# IceLogicBus.net
KiCad netlist of a schematic drawn in EAGLE
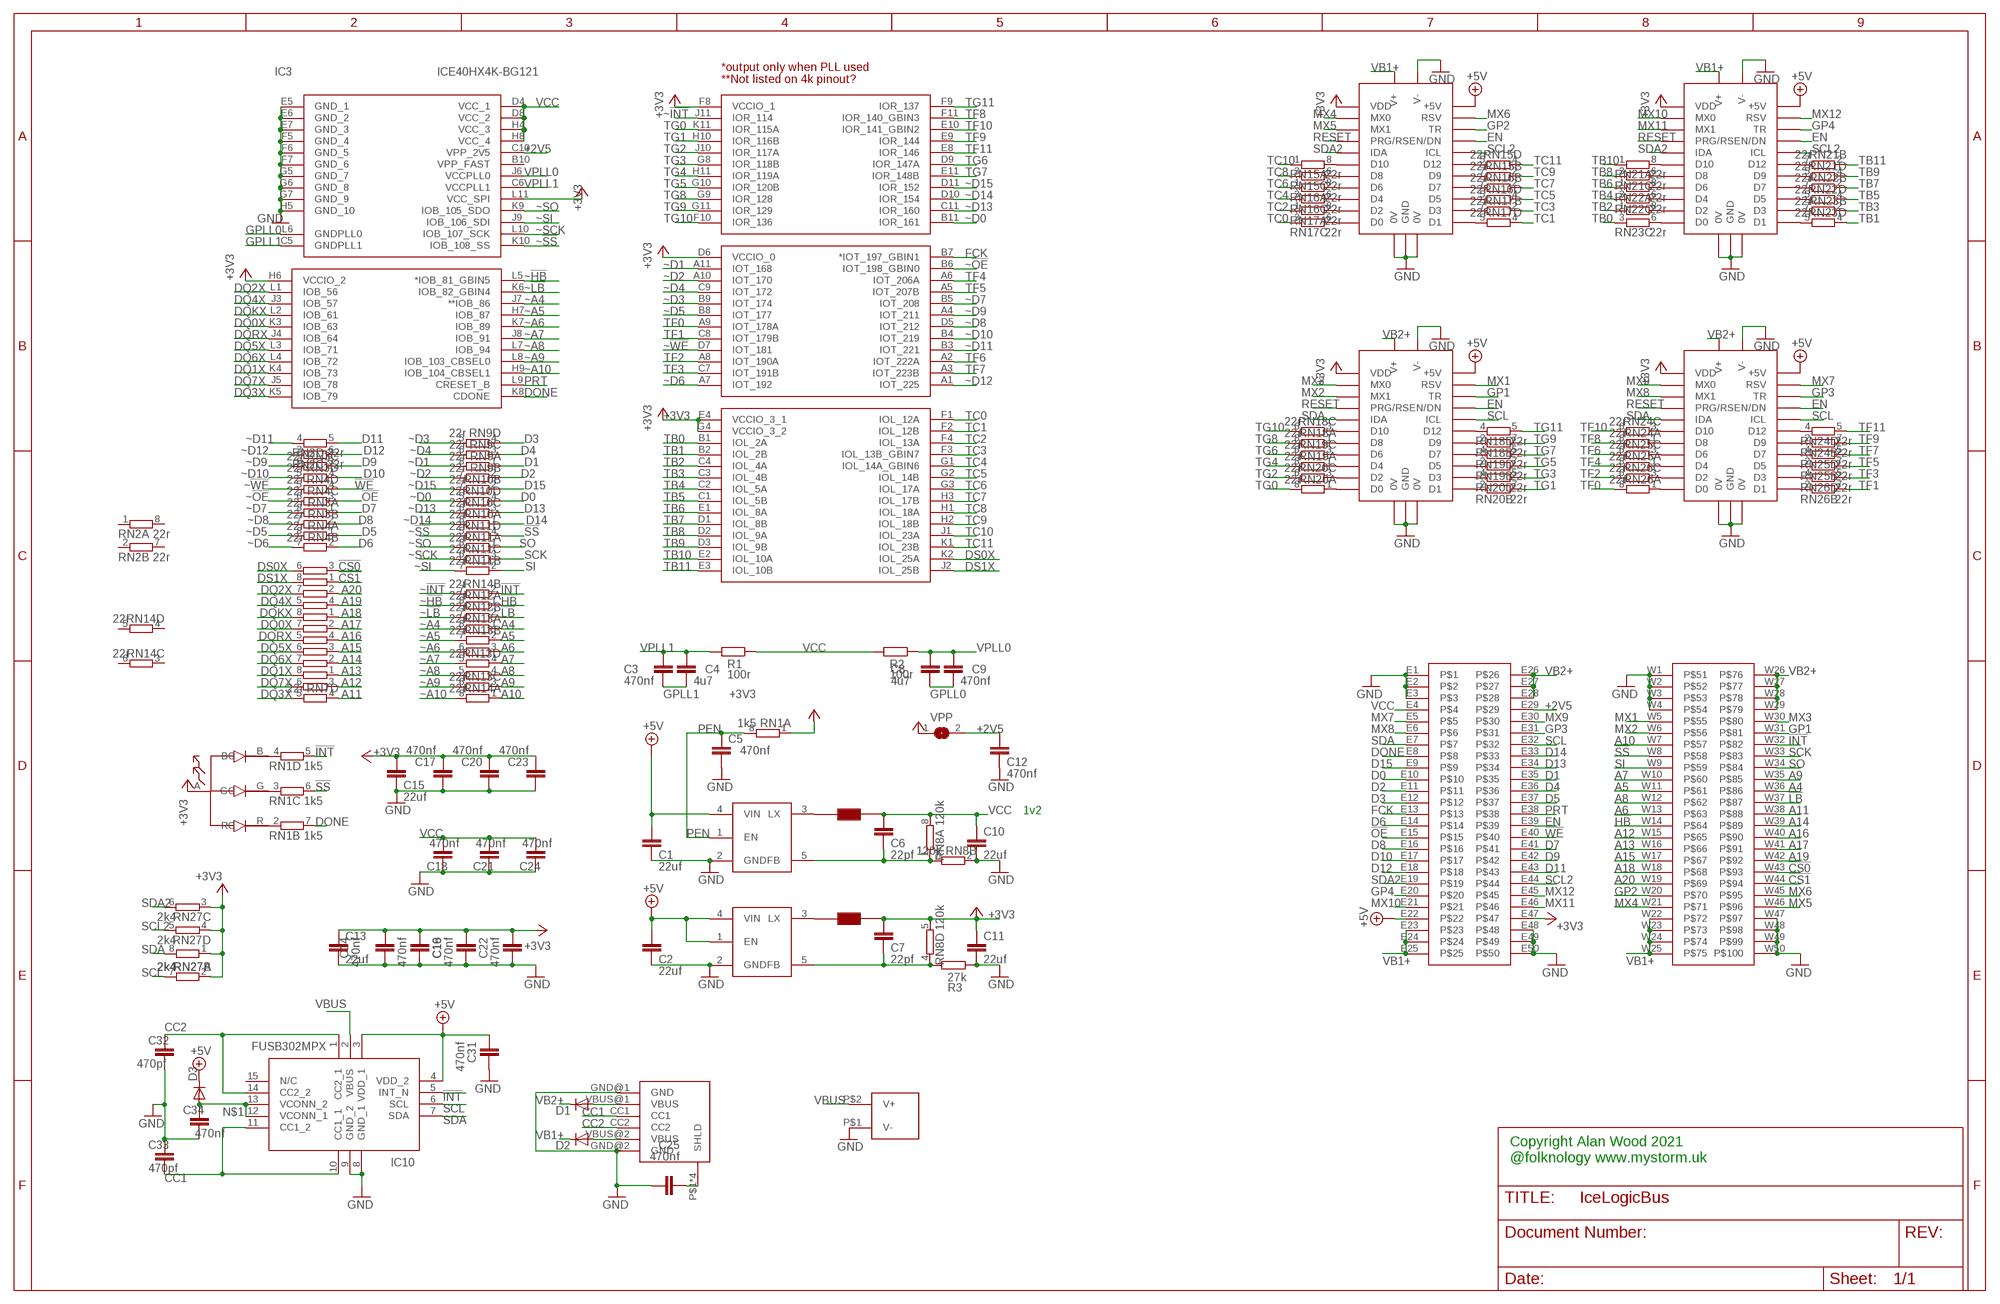
[diagram p0: schematic, sheet 1]

(export (version "E")
  (design (tool "Eeschema 10.0.6"))
  (components
    (comp (ref "C1")
      (value "22uf")
      (footprint "eagle-import:C0603")
      (libsource (lib "eagle-import") (part "C-EUC0603"))
    )
    (comp (ref "C2")
      (value "22uf")
      (footprint "eagle-import:C0603")
      (libsource (lib "eagle-import") (part "C-EUC0603"))
    )
    (comp (ref "C3")
      (value "470nf")
      (footprint "eagle-import:C0402")
      (libsource (lib "eagle-import") (part "C-EUC0402"))
    )
    (comp (ref "C4")
      (value "4u7")
      (footprint "eagle-import:C0402")
      (libsource (lib "eagle-import") (part "C-EUC0402"))
    )
    (comp (ref "C5")
      (value "470nf")
      (footprint "eagle-import:C0402")
      (libsource (lib "eagle-import") (part "C-EUC0402"))
    )
    (comp (ref "C6")
      (value "22pf")
      (footprint "eagle-import:C0402")
      (libsource (lib "eagle-import") (part "C-EUC0402"))
    )
    (comp (ref "C7")
      (value "22pf")
      (footprint "eagle-import:C0402")
      (libsource (lib "eagle-import") (part "C-EUC0402"))
    )
    (comp (ref "C8")
      (value "4u7")
      (footprint "eagle-import:C0402")
      (libsource (lib "eagle-import") (part "C-EUC0402"))
    )
    (comp (ref "C9")
      (value "470nf")
      (footprint "eagle-import:C0402")
      (libsource (lib "eagle-import") (part "C-EUC0402"))
    )
    (comp (ref "C10")
      (value "22uf")
      (footprint "eagle-import:C0603")
      (libsource (lib "eagle-import") (part "C-EUC0603"))
    )
    (comp (ref "C11")
      (value "22uf")
      (footprint "eagle-import:C0603")
      (libsource (lib "eagle-import") (part "C-EUC0603"))
    )
    (comp (ref "C12")
      (value "470nf")
      (footprint "eagle-import:C0402")
      (libsource (lib "eagle-import") (part "C-EUC0402"))
    )
    (comp (ref "C13")
      (value "22uf")
      (footprint "eagle-import:C0603")
      (libsource (lib "eagle-import") (part "C-EUC0603"))
    )
    (comp (ref "C14")
      (value "470nf")
      (footprint "eagle-import:C0402")
      (libsource (lib "eagle-import") (part "C-EUC0402"))
    )
    (comp (ref "C15")
      (value "22uf")
      (footprint "eagle-import:C0603")
      (libsource (lib "eagle-import") (part "C-EUC0603"))
    )
    (comp (ref "C16")
      (value "470nf")
      (footprint "eagle-import:C0402")
      (libsource (lib "eagle-import") (part "C-EUC0402"))
    )
    (comp (ref "C17")
      (value "470nf")
      (footprint "eagle-import:C0402")
      (libsource (lib "eagle-import") (part "C-EUC0402"))
    )
    (comp (ref "C18")
      (value "470nf")
      (footprint "eagle-import:C0402")
      (libsource (lib "eagle-import") (part "C-EUC0402"))
    )
    (comp (ref "C19")
      (value "470nf")
      (footprint "eagle-import:C0402")
      (libsource (lib "eagle-import") (part "C-EUC0402"))
    )
    (comp (ref "C20")
      (value "470nf")
      (footprint "eagle-import:C0402")
      (libsource (lib "eagle-import") (part "C-EUC0402"))
    )
    (comp (ref "C21")
      (value "470nf")
      (footprint "eagle-import:C0402")
      (libsource (lib "eagle-import") (part "C-EUC0402"))
    )
    (comp (ref "C22")
      (value "470nf")
      (footprint "eagle-import:C0402")
      (libsource (lib "eagle-import") (part "C-EUC0402"))
    )
    (comp (ref "C23")
      (value "470nf")
      (footprint "eagle-import:C0402")
      (libsource (lib "eagle-import") (part "C-EUC0402"))
    )
    (comp (ref "C24")
      (value "470nf")
      (footprint "eagle-import:C0402")
      (libsource (lib "eagle-import") (part "C-EUC0402"))
    )
    (comp (ref "C25")
      (value "470nf")
      (footprint "eagle-import:C0402")
      (libsource (lib "eagle-import") (part "C-EUC0402"))
    )
    (comp (ref "C31")
      (value "470nf")
      (footprint "eagle-import:C0402")
      (libsource (lib "eagle-import") (part "C-EUC0402"))
    )
    (comp (ref "C32")
      (value "470pf")
      (footprint "eagle-import:C0402")
      (libsource (lib "eagle-import") (part "C-EUC0402"))
    )
    (comp (ref "C33")
      (value "470pf")
      (footprint "eagle-import:C0402")
      (libsource (lib "eagle-import") (part "C-EUC0402"))
    )
    (comp (ref "C34")
      (value "470nf")
      (footprint "eagle-import:C0402")
      (libsource (lib "eagle-import") (part "C-EUC0402"))
    )
    (comp (ref "D1")
      (value "DIODE-SOD123")
      (footprint "eagle-import:SOD123")
      (libsource (lib "eagle-import") (part "DIODE-SOD123"))
    )
    (comp (ref "D2")
      (value "DIODE-SOD123")
      (footprint "eagle-import:SOD123")
      (libsource (lib "eagle-import") (part "DIODE-SOD123"))
    )
    (comp (ref "D3")
      (value "DIODE-SOD323-W")
      (footprint "eagle-import:SOD323-W")
      (libsource (lib "eagle-import") (part "DIODE-SOD323-W"))
    )
    (comp (ref "IC1")
      (value "AP3429/A")
      (footprint "eagle-import:TSOP-5_SOT23-5")
      (libsource (lib "eagle-import") (part "AP3429/A"))
    )
    (comp (ref "IC2")
      (value "AP3429/A")
      (footprint "eagle-import:TSOP-5_SOT23-5")
      (libsource (lib "eagle-import") (part "AP3429/A"))
    )
    (comp (ref "IC3")
      (value "ICE40HX4K-BG121")
      (footprint "eagle-import:BGA121C80P11X11_900X900X110")
      (fields (field (name "MOUSER_PART_NUMBER") "842-ICE40HX4K-BG121"))
      (libsource (lib "eagle-import") (part "ICE40HX4K-BG121"))
    )
    (comp (ref "IC10")
      (value "FUSB302MPX")
      (footprint "eagle-import:QFN50P250X250X80-15N")
      (fields (field (name "MOUSER_PART_NUMBER") "512-FUSB302MPX"))
      (libsource (lib "eagle-import") (part "FUSB302MPX"))
    )
    (comp (ref "L1")
      (value "NRS4018")
      (footprint "eagle-import:NRC4018")
      (libsource (lib "eagle-import") (part "NRS4018"))
    )
    (comp (ref "L2")
      (value "NRS4018")
      (footprint "eagle-import:NRC4018")
      (libsource (lib "eagle-import") (part "NRS4018"))
    )
    (comp (ref "L3")
      (value "RGB_LED")
      (footprint "eagle-import:RGB_LED_IMM")
      (libsource (lib "eagle-import") (part "RGB_LED"))
    )
    (comp (ref "R1")
      (value "100r")
      (footprint "eagle-import:R0402")
      (libsource (lib "eagle-import") (part "R-EU_R0402"))
    )
    (comp (ref "R2")
      (value "100r")
      (footprint "eagle-import:R0402")
      (libsource (lib "eagle-import") (part "R-EU_R0402"))
    )
    (comp (ref "R3")
      (value "27k")
      (footprint "eagle-import:R0402")
      (libsource (lib "eagle-import") (part "R-EU_R0402"))
    )
    (comp (ref "RN1")
      (value "1k5")
      (footprint "eagle-import:EXB38V")
      (libsource (lib "eagle-import") (part "4R-NEXB38V"))
    )
    (comp (ref "RN2")
      (value "22r")
      (footprint "eagle-import:EXB38V")
      (libsource (lib "eagle-import") (part "4R-NEXB38V"))
    )
    (comp (ref "RN3")
      (value "22r")
      (footprint "eagle-import:EXB38V")
      (libsource (lib "eagle-import") (part "4R-NEXB38V"))
    )
    (comp (ref "RN4")
      (value "22r")
      (footprint "eagle-import:EXB38V")
      (libsource (lib "eagle-import") (part "4R-NEXB38V"))
    )
    (comp (ref "RN5")
      (value "22r")
      (footprint "eagle-import:EXB38V")
      (libsource (lib "eagle-import") (part "4R-NEXB38V"))
    )
    (comp (ref "RN6")
      (value "22r")
      (footprint "eagle-import:EXB38V")
      (libsource (lib "eagle-import") (part "4R-NEXB38V"))
    )
    (comp (ref "RN7")
      (value "22r")
      (footprint "eagle-import:EXB38V")
      (libsource (lib "eagle-import") (part "4R-NEXB38V"))
    )
    (comp (ref "RN8")
      (value "120k")
      (footprint "eagle-import:EXB38V")
      (libsource (lib "eagle-import") (part "4R-NEXB38V"))
    )
    (comp (ref "RN9")
      (value "22r")
      (footprint "eagle-import:EXB38V")
      (libsource (lib "eagle-import") (part "4R-NEXB38V"))
    )
    (comp (ref "RN10")
      (value "22r")
      (footprint "eagle-import:EXB38V")
      (libsource (lib "eagle-import") (part "4R-NEXB38V"))
    )
    (comp (ref "RN11")
      (value "22r")
      (footprint "eagle-import:EXB38V")
      (libsource (lib "eagle-import") (part "4R-NEXB38V"))
    )
    (comp (ref "RN12")
      (value "22r")
      (footprint "eagle-import:EXB38V")
      (libsource (lib "eagle-import") (part "4R-NEXB38V"))
    )
    (comp (ref "RN13")
      (value "22r")
      (footprint "eagle-import:EXB38V")
      (libsource (lib "eagle-import") (part "4R-NEXB38V"))
    )
    (comp (ref "RN14")
      (value "22r")
      (footprint "eagle-import:EXB38V")
      (libsource (lib "eagle-import") (part "4R-NEXB38V"))
    )
    (comp (ref "RN15")
      (value "22r")
      (footprint "eagle-import:EXB38V")
      (libsource (lib "eagle-import") (part "4R-NEXB38V"))
    )
    (comp (ref "RN16")
      (value "22r")
      (footprint "eagle-import:EXB38V")
      (libsource (lib "eagle-import") (part "4R-NEXB38V"))
    )
    (comp (ref "RN17")
      (value "22r")
      (footprint "eagle-import:EXB38V")
      (libsource (lib "eagle-import") (part "4R-NEXB38V"))
    )
    (comp (ref "RN18")
      (value "22r")
      (footprint "eagle-import:EXB38V")
      (libsource (lib "eagle-import") (part "4R-NEXB38V"))
    )
    (comp (ref "RN19")
      (value "22r")
      (footprint "eagle-import:EXB38V")
      (libsource (lib "eagle-import") (part "4R-NEXB38V"))
    )
    (comp (ref "RN20")
      (value "22r")
      (footprint "eagle-import:EXB38V")
      (libsource (lib "eagle-import") (part "4R-NEXB38V"))
    )
    (comp (ref "RN21")
      (value "22r")
      (footprint "eagle-import:EXB38V")
      (libsource (lib "eagle-import") (part "4R-NEXB38V"))
    )
    (comp (ref "RN22")
      (value "22r")
      (footprint "eagle-import:EXB38V")
      (libsource (lib "eagle-import") (part "4R-NEXB38V"))
    )
    (comp (ref "RN23")
      (value "22r")
      (footprint "eagle-import:EXB38V")
      (libsource (lib "eagle-import") (part "4R-NEXB38V"))
    )
    (comp (ref "RN24")
      (value "22r")
      (footprint "eagle-import:EXB38V")
      (libsource (lib "eagle-import") (part "4R-NEXB38V"))
    )
    (comp (ref "RN25")
      (value "22r")
      (footprint "eagle-import:EXB38V")
      (libsource (lib "eagle-import") (part "4R-NEXB38V"))
    )
    (comp (ref "RN26")
      (value "22r")
      (footprint "eagle-import:EXB38V")
      (libsource (lib "eagle-import") (part "4R-NEXB38V"))
    )
    (comp (ref "RN27")
      (value "2k4")
      (footprint "eagle-import:EXB38V")
      (libsource (lib "eagle-import") (part "4R-NEXB38V"))
    )
    (comp (ref "T1")
      (value "UTILE_LPCARRIER_SMD_MALE_1.27")
      (footprint "eagle-import:UTILE_LP")
      (libsource (lib "eagle-import") (part "UTILE_LPCARRIER_SMD_MALE_1.27"))
    )
    (comp (ref "T2")
      (value "UTILE_LPCARRIER_SMD_MALE_1.27")
      (footprint "eagle-import:UTILE_LP")
      (libsource (lib "eagle-import") (part "UTILE_LPCARRIER_SMD_MALE_1.27"))
    )
    (comp (ref "T3")
      (value "MEZZANINE")
      (footprint "eagle-import:MEZZANINE")
      (libsource (lib "eagle-import") (part "MEZZANINE"))
    )
    (comp (ref "T4")
      (value "UTILE_LPCARRIER_SMD_MALE_1.27")
      (footprint "eagle-import:UTILE_LP")
      (libsource (lib "eagle-import") (part "UTILE_LPCARRIER_SMD_MALE_1.27"))
    )
    (comp (ref "T5")
      (value "UTILE_LPCARRIER_SMD_MALE_1.27")
      (footprint "eagle-import:UTILE_LP")
      (libsource (lib "eagle-import") (part "UTILE_LPCARRIER_SMD_MALE_1.27"))
    )
    (comp (ref "U$1")
      (value "USB-C-6")
      (footprint "eagle-import:USB-C-6")
      (libsource (lib "eagle-import") (part "USB-C-6"))
    )
    (comp (ref "U$2")
      (value "XT-XXXT")
      (footprint "eagle-import:XT30PW-M")
      (libsource (lib "eagle-import") (part "XT-XXXT"))
    )
    (comp (ref "VPP") (value "SJ") (footprint "eagle-import:SJ") (libsource (lib "eagle-import") (part "SJ")))
  )
  (nets
    (net (code "1") (name "+3V3") (class "Default")
      (node (ref "C11") (pin "1") (pinfunction "1_1") (pintype "passive"))
      (node (ref "C13") (pin "1") (pinfunction "1_1") (pintype "passive"))
      (node (ref "C14") (pin "2") (pinfunction "2_2") (pintype "passive"))
      (node (ref "C15") (pin "2") (pinfunction "2_2") (pintype "passive"))
      (node (ref "C16") (pin "2") (pinfunction "2_2") (pintype "passive"))
      (node (ref "C17") (pin "1") (pinfunction "1_1") (pintype "passive"))
      (node (ref "C19") (pin "2") (pinfunction "2_2") (pintype "passive"))
      (node (ref "C20") (pin "1") (pinfunction "1_1") (pintype "passive"))
      (node (ref "C22") (pin "2") (pinfunction "2_2") (pintype "passive"))
      (node (ref "C23") (pin "1") (pinfunction "1_1") (pintype "passive"))
      (node (ref "C7") (pin "2") (pinfunction "2_2") (pintype "passive"))
      (node (ref "IC3") (pin "D6") (pinfunction "VCCIO_0_D6") (pintype "bidirectional"))
      (node (ref "IC3") (pin "E4") (pinfunction "VCCIO_3_1_E4") (pintype "bidirectional"))
      (node (ref "IC3") (pin "F8") (pinfunction "VCCIO_1_F8") (pintype "bidirectional"))
      (node (ref "IC3") (pin "G4") (pinfunction "VCCIO_3_2_G4") (pintype "bidirectional"))
      (node (ref "IC3") (pin "H6") (pinfunction "VCCIO_2_H6") (pintype "bidirectional"))
      (node (ref "IC3") (pin "L11") (pinfunction "VCC_SPI_L11") (pintype "bidirectional"))
      (node (ref "L2") (pin "P$2") (pinfunction "P$2_P$2") (pintype "passive"))
      (node (ref "L3") (pin "A") (pinfunction "ANODE_A") (pintype "bidirectional"))
      (node (ref "RN1") (pin "1") (pinfunction "1_1") (pintype "passive"))
      (node (ref "RN27") (pin "1") (pinfunction "1_1") (pintype "passive"))
      (node (ref "RN27") (pin "2") (pinfunction "1_2") (pintype "passive"))
      (node (ref "RN27") (pin "3") (pinfunction "1_3") (pintype "passive"))
      (node (ref "RN27") (pin "4") (pinfunction "1_4") (pintype "passive"))
      (node (ref "RN8") (pin "5") (pinfunction "2_5") (pintype "passive"))
      (node (ref "T1") (pin "P$18") (pinfunction "VDD_P$18") (pintype "power_in"))
      (node (ref "T2") (pin "P$18") (pinfunction "VDD_P$18") (pintype "power_in"))
      (node (ref "T3") (pin "E47") (pinfunction "P$47_E47") (pintype "bidirectional"))
      (node (ref "T4") (pin "P$18") (pinfunction "VDD_P$18") (pintype "power_in"))
      (node (ref "T5") (pin "P$18") (pinfunction "VDD_P$18") (pintype "power_in"))
      (node (ref "VPP") (pin "1") (pinfunction "1_1") (pintype "passive"))
    )
    (net (code "2") (name "+5V") (class "Default")
      (node (ref "C1") (pin "2") (pinfunction "2_2") (pintype "passive"))
      (node (ref "C2") (pin "2") (pinfunction "2_2") (pintype "passive"))
      (node (ref "C31") (pin "2") (pinfunction "2_2") (pintype "passive"))
      (node (ref "D3") (pin "C") (pinfunction "C_C") (pintype "passive"))
      (node (ref "IC1") (pin "4") (pinfunction "VIN_4") (pintype "power_in"))
      (node (ref "IC10") (pin "3") (pinfunction "VDD_1_3") (pintype "bidirectional"))
      (node (ref "IC10") (pin "4") (pinfunction "VDD_2_4") (pintype "bidirectional"))
      (node (ref "IC2") (pin "1") (pinfunction "EN_1") (pintype "input"))
      (node (ref "IC2") (pin "4") (pinfunction "VIN_4") (pintype "power_in"))
      (node (ref "T1") (pin "P$43") (pinfunction "+5V_P$43") (pintype "power_in"))
      (node (ref "T2") (pin "P$43") (pinfunction "+5V_P$43") (pintype "power_in"))
      (node (ref "T3") (pin "E22") (pinfunction "P$22_E22") (pintype "bidirectional"))
      (node (ref "T4") (pin "P$43") (pinfunction "+5V_P$43") (pintype "power_in"))
      (node (ref "T5") (pin "P$43") (pinfunction "+5V_P$43") (pintype "power_in"))
    )
    (net (code "3") (name "/+2V5") (class "Default")
      (node (ref "C12") (pin "2") (pinfunction "2_2") (pintype "passive"))
      (node (ref "IC3") (pin "C10") (pinfunction "VPP_2V5_C10") (pintype "bidirectional"))
      (node (ref "T3") (pin "E29") (pinfunction "P$29_E29") (pintype "bidirectional"))
      (node (ref "VPP") (pin "2") (pinfunction "2_2") (pintype "passive"))
    )
    (net (code "4") (name "/A4") (class "Default")
      (node (ref "RN13") (pin "1") (pinfunction "1_1") (pintype "passive"))
      (node (ref "T3") (pin "W36") (pinfunction "P$86_W36") (pintype "bidirectional"))
    )
    (net (code "5") (name "/A5") (class "Default")
      (node (ref "RN13") (pin "2") (pinfunction "1_2") (pintype "passive"))
      (node (ref "T3") (pin "W11") (pinfunction "P$61_W11") (pintype "bidirectional"))
    )
    (net (code "6") (name "/A6") (class "Default")
      (node (ref "RN12") (pin "3") (pinfunction "1_3") (pintype "passive"))
      (node (ref "T3") (pin "W13") (pinfunction "P$63_W13") (pintype "bidirectional"))
    )
    (net (code "7") (name "/A7") (class "Default")
      (node (ref "RN13") (pin "4") (pinfunction "1_4") (pintype "passive"))
      (node (ref "T3") (pin "W10") (pinfunction "P$60_W10") (pintype "bidirectional"))
    )
    (net (code "8") (name "/A8") (class "Default")
      (node (ref "RN12") (pin "4") (pinfunction "1_4") (pintype "passive"))
      (node (ref "T3") (pin "W12") (pinfunction "P$62_W12") (pintype "bidirectional"))
    )
    (net (code "9") (name "/A9") (class "Default")
      (node (ref "RN13") (pin "3") (pinfunction "1_3") (pintype "passive"))
      (node (ref "T3") (pin "W35") (pinfunction "P$85_W35") (pintype "bidirectional"))
    )
    (net (code "10") (name "/A10") (class "Default")
      (node (ref "RN14") (pin "1") (pinfunction "1_1") (pintype "passive"))
      (node (ref "T3") (pin "W7") (pinfunction "P$57_W7") (pintype "bidirectional"))
    )
    (net (code "11") (name "/A11") (class "Default")
      (node (ref "RN7") (pin "4") (pinfunction "1_4") (pintype "passive"))
      (node (ref "T3") (pin "W38") (pinfunction "P$88_W38") (pintype "bidirectional"))
    )
    (net (code "12") (name "/A12") (class "Default")
      (node (ref "RN7") (pin "3") (pinfunction "1_3") (pintype "passive"))
      (node (ref "T3") (pin "W15") (pinfunction "P$65_W15") (pintype "bidirectional"))
    )
    (net (code "13") (name "/A13") (class "Default")
      (node (ref "RN7") (pin "1") (pinfunction "1_1") (pintype "passive"))
      (node (ref "T3") (pin "W16") (pinfunction "P$66_W16") (pintype "bidirectional"))
    )
    (net (code "14") (name "/A14") (class "Default")
      (node (ref "RN7") (pin "2") (pinfunction "1_2") (pintype "passive"))
      (node (ref "T3") (pin "W39") (pinfunction "P$89_W39") (pintype "bidirectional"))
    )
    (net (code "15") (name "/A15") (class "Default")
      (node (ref "RN6") (pin "3") (pinfunction "1_3") (pintype "passive"))
      (node (ref "T3") (pin "W17") (pinfunction "P$67_W17") (pintype "bidirectional"))
    )
    (net (code "16") (name "/A16") (class "Default")
      (node (ref "RN6") (pin "4") (pinfunction "1_4") (pintype "passive"))
      (node (ref "T3") (pin "W40") (pinfunction "P$90_W40") (pintype "bidirectional"))
    )
    (net (code "17") (name "/A17") (class "Default")
      (node (ref "RN6") (pin "2") (pinfunction "1_2") (pintype "passive"))
      (node (ref "T3") (pin "W41") (pinfunction "P$91_W41") (pintype "bidirectional"))
    )
    (net (code "18") (name "/A18") (class "Default")
      (node (ref "RN6") (pin "1") (pinfunction "1_1") (pintype "passive"))
      (node (ref "T3") (pin "W18") (pinfunction "P$68_W18") (pintype "bidirectional"))
    )
    (net (code "19") (name "/A19") (class "Default")
      (node (ref "RN5") (pin "4") (pinfunction "1_4") (pintype "passive"))
      (node (ref "T3") (pin "W42") (pinfunction "P$92_W42") (pintype "bidirectional"))
    )
    (net (code "20") (name "/A20") (class "Default")
      (node (ref "RN5") (pin "2") (pinfunction "1_2") (pintype "passive"))
      (node (ref "T3") (pin "W19") (pinfunction "P$69_W19") (pintype "bidirectional"))
    )
    (net (code "21") (name "/CC1") (class "Default")
      (node (ref "C33") (pin "1") (pinfunction "1_1") (pintype "passive"))
      (node (ref "IC10") (pin "10") (pinfunction "CC1_1_10") (pintype "bidirectional"))
      (node (ref "IC10") (pin "11") (pinfunction "CC1_2_11") (pintype "bidirectional"))
      (node (ref "U$1") (pin "CC1") (pinfunction "CC1_CC1") (pintype "bidirectional"))
    )
    (net (code "22") (name "/CC2") (class "Default")
      (node (ref "C32") (pin "2") (pinfunction "2_2") (pintype "passive"))
      (node (ref "IC10") (pin "1") (pinfunction "CC2_1_1") (pintype "bidirectional"))
      (node (ref "IC10") (pin "14") (pinfunction "CC2_2_14") (pintype "bidirectional"))
      (node (ref "U$1") (pin "CC2") (pinfunction "CC2_CC2") (pintype "bidirectional"))
    )
    (net (code "23") (name "/D0") (class "Default")
      (node (ref "RN10") (pin "4") (pinfunction "1_4") (pintype "passive"))
      (node (ref "T3") (pin "E10") (pinfunction "P$10_E10") (pintype "bidirectional"))
    )
    (net (code "24") (name "/D1") (class "Default")
      (node (ref "RN9") (pin "1") (pinfunction "1_1") (pintype "passive"))
      (node (ref "T3") (pin "E35") (pinfunction "P$35_E35") (pintype "bidirectional"))
    )
    (net (code "25") (name "/D2") (class "Default")
      (node (ref "RN9") (pin "2") (pinfunction "1_2") (pintype "passive"))
      (node (ref "T3") (pin "E11") (pinfunction "P$11_E11") (pintype "bidirectional"))
    )
    (net (code "26") (name "/D3") (class "Default")
      (node (ref "RN9") (pin "4") (pinfunction "1_4") (pintype "passive"))
      (node (ref "T3") (pin "E12") (pinfunction "P$12_E12") (pintype "bidirectional"))
    )
    (net (code "27") (name "/D4") (class "Default")
      (node (ref "RN9") (pin "3") (pinfunction "1_3") (pintype "passive"))
      (node (ref "T3") (pin "E36") (pinfunction "P$36_E36") (pintype "bidirectional"))
    )
    (net (code "28") (name "/D5") (class "Default")
      (node (ref "RN4") (pin "1") (pinfunction "1_1") (pintype "passive"))
      (node (ref "T3") (pin "E37") (pinfunction "P$37_E37") (pintype "bidirectional"))
    )
    (net (code "29") (name "/D6") (class "Default")
      (node (ref "RN4") (pin "2") (pinfunction "1_2") (pintype "passive"))
      (node (ref "T3") (pin "E14") (pinfunction "P$14_E14") (pintype "bidirectional"))
    )
    (net (code "30") (name "/D7") (class "Default")
      (node (ref "RN3") (pin "1") (pinfunction "1_1") (pintype "passive"))
      (node (ref "T3") (pin "E41") (pinfunction "P$41_E41") (pintype "bidirectional"))
    )
    (net (code "31") (name "/D8") (class "Default")
      (node (ref "RN3") (pin "2") (pinfunction "1_2") (pintype "passive"))
      (node (ref "T3") (pin "E16") (pinfunction "P$16_E16") (pintype "bidirectional"))
    )
    (net (code "32") (name "/D9") (class "Default")
      (node (ref "RN3") (pin "3") (pinfunction "1_3") (pintype "passive"))
      (node (ref "T3") (pin "E42") (pinfunction "P$42_E42") (pintype "bidirectional"))
    )
    (net (code "33") (name "/D10") (class "Default")
      (node (ref "RN3") (pin "4") (pinfunction "1_4") (pintype "passive"))
      (node (ref "T3") (pin "E17") (pinfunction "P$17_E17") (pintype "bidirectional"))
    )
    (net (code "34") (name "/D11") (class "Default")
      (node (ref "RN2") (pin "5") (pinfunction "2_5") (pintype "passive"))
      (node (ref "T3") (pin "E43") (pinfunction "P$43_E43") (pintype "bidirectional"))
    )
    (net (code "35") (name "/D12") (class "Default")
      (node (ref "RN2") (pin "6") (pinfunction "2_6") (pintype "passive"))
      (node (ref "T3") (pin "E18") (pinfunction "P$18_E18") (pintype "bidirectional"))
    )
    (net (code "36") (name "/D13") (class "Default")
      (node (ref "RN10") (pin "3") (pinfunction "1_3") (pintype "passive"))
      (node (ref "T3") (pin "E34") (pinfunction "P$34_E34") (pintype "bidirectional"))
    )
    (net (code "37") (name "/D14") (class "Default")
      (node (ref "RN10") (pin "1") (pinfunction "1_1") (pintype "passive"))
      (node (ref "T3") (pin "E33") (pinfunction "P$33_E33") (pintype "bidirectional"))
    )
    (net (code "38") (name "/D15") (class "Default")
      (node (ref "RN10") (pin "2") (pinfunction "1_2") (pintype "passive"))
      (node (ref "T3") (pin "E9") (pinfunction "P$9_E9") (pintype "bidirectional"))
    )
    (net (code "39") (name "/DONE") (class "Default")
      (node (ref "IC3") (pin "K8") (pinfunction "CDONE_K8") (pintype "bidirectional"))
      (node (ref "RN1") (pin "7") (pinfunction "2_7") (pintype "passive"))
      (node (ref "T3") (pin "E8") (pinfunction "P$8_E8") (pintype "bidirectional"))
    )
    (net (code "40") (name "/DQ0X") (class "Default")
      (node (ref "IC3") (pin "K3") (pinfunction "IOB_63_K3") (pintype "bidirectional"))
      (node (ref "RN6") (pin "7") (pinfunction "2_7") (pintype "passive"))
    )
    (net (code "41") (name "/DQ1X") (class "Default")
      (node (ref "IC3") (pin "K4") (pinfunction "IOB_73_K4") (pintype "bidirectional"))
      (node (ref "RN7") (pin "8") (pinfunction "2_8") (pintype "passive"))
    )
    (net (code "42") (name "/DQ2X") (class "Default")
      (node (ref "IC3") (pin "L1") (pinfunction "IOB_56_L1") (pintype "bidirectional"))
      (node (ref "RN5") (pin "7") (pinfunction "2_7") (pintype "passive"))
    )
    (net (code "43") (name "/DQ3X") (class "Default")
      (node (ref "IC3") (pin "K5") (pinfunction "IOB_79_K5") (pintype "bidirectional"))
      (node (ref "RN7") (pin "5") (pinfunction "2_5") (pintype "passive"))
    )
    (net (code "44") (name "/DQ4X") (class "Default")
      (node (ref "IC3") (pin "J3") (pinfunction "IOB_57_J3") (pintype "bidirectional"))
      (node (ref "RN5") (pin "5") (pinfunction "2_5") (pintype "passive"))
    )
    (net (code "45") (name "/DQ5X") (class "Default")
      (node (ref "IC3") (pin "L3") (pinfunction "IOB_71_L3") (pintype "bidirectional"))
      (node (ref "RN6") (pin "6") (pinfunction "2_6") (pintype "passive"))
    )
    (net (code "46") (name "/DQ6X") (class "Default")
      (node (ref "IC3") (pin "L4") (pinfunction "IOB_72_L4") (pintype "bidirectional"))
      (node (ref "RN7") (pin "7") (pinfunction "2_7") (pintype "passive"))
    )
    (net (code "47") (name "/DQ7X") (class "Default")
      (node (ref "IC3") (pin "J5") (pinfunction "IOB_78_J5") (pintype "bidirectional"))
      (node (ref "RN7") (pin "6") (pinfunction "2_6") (pintype "passive"))
    )
    (net (code "48") (name "/DQKX") (class "Default")
      (node (ref "IC3") (pin "L2") (pinfunction "IOB_61_L2") (pintype "bidirectional"))
      (node (ref "RN6") (pin "8") (pinfunction "2_8") (pintype "passive"))
    )
    (net (code "49") (name "/DQRX") (class "Default")
      (node (ref "IC3") (pin "J4") (pinfunction "IOB_64_J4") (pintype "bidirectional"))
      (node (ref "RN6") (pin "5") (pinfunction "2_5") (pintype "passive"))
    )
    (net (code "50") (name "/DS0X") (class "Default")
      (node (ref "IC3") (pin "K2") (pinfunction "IOL_25A_K2") (pintype "bidirectional"))
      (node (ref "RN5") (pin "6") (pinfunction "2_6") (pintype "passive"))
    )
    (net (code "51") (name "/DS1X") (class "Default")
      (node (ref "IC3") (pin "J2") (pinfunction "IOL_25B_J2") (pintype "bidirectional"))
      (node (ref "RN5") (pin "8") (pinfunction "2_8") (pintype "passive"))
    )
    (net (code "52") (name "/EN") (class "Default")
      (node (ref "T1") (pin "P$40") (pinfunction "EN/DN_P$40") (pintype "open_collector"))
      (node (ref "T2") (pin "P$40") (pinfunction "EN/DN_P$40") (pintype "open_collector"))
      (node (ref "T3") (pin "E39") (pinfunction "P$39_E39") (pintype "bidirectional"))
      (node (ref "T4") (pin "P$40") (pinfunction "EN/DN_P$40") (pintype "open_collector"))
      (node (ref "T5") (pin "P$40") (pinfunction "EN/DN_P$40") (pintype "open_collector"))
    )
    (net (code "53") (name "/FCK") (class "Default")
      (node (ref "IC3") (pin "B7") (pinfunction "*IOT_197_GBIN1_B7") (pintype "bidirectional"))
      (node (ref "T3") (pin "E13") (pinfunction "P$13_E13") (pintype "bidirectional"))
    )
    (net (code "54") (name "/GP1") (class "Default")
      (node (ref "T2") (pin "P$41") (pinfunction "TR_P$41") (pintype "bidirectional"))
      (node (ref "T3") (pin "W31") (pinfunction "P$81_W31") (pintype "bidirectional"))
    )
    (net (code "55") (name "/GP2") (class "Default")
      (node (ref "T1") (pin "P$41") (pinfunction "TR_P$41") (pintype "bidirectional"))
      (node (ref "T3") (pin "W20") (pinfunction "P$70_W20") (pintype "bidirectional"))
    )
    (net (code "56") (name "/GP3") (class "Default")
      (node (ref "T3") (pin "E31") (pinfunction "P$31_E31") (pintype "bidirectional"))
      (node (ref "T5") (pin "P$41") (pinfunction "TR_P$41") (pintype "bidirectional"))
    )
    (net (code "57") (name "/GP4") (class "Default")
      (node (ref "T3") (pin "E20") (pinfunction "P$20_E20") (pintype "bidirectional"))
      (node (ref "T4") (pin "P$41") (pinfunction "TR_P$41") (pintype "bidirectional"))
    )
    (net (code "58") (name "/GPLL0") (class "Default")
      (node (ref "C8") (pin "1") (pinfunction "1_1") (pintype "passive"))
      (node (ref "C9") (pin "1") (pinfunction "1_1") (pintype "passive"))
      (node (ref "IC3") (pin "L6") (pinfunction "GNDPLL0_L6") (pintype "bidirectional"))
    )
    (net (code "59") (name "/GPLL1") (class "Default")
      (node (ref "C3") (pin "1") (pinfunction "1_1") (pintype "passive"))
      (node (ref "C4") (pin "1") (pinfunction "1_1") (pintype "passive"))
      (node (ref "IC3") (pin "C5") (pinfunction "GNDPLL1_C5") (pintype "bidirectional"))
    )
    (net (code "60") (name "/MX1") (class "Default")
      (node (ref "T2") (pin "P$42") (pinfunction "RSV_P$42") (pintype "bidirectional"))
      (node (ref "T3") (pin "W5") (pinfunction "P$55_W5") (pintype "bidirectional"))
    )
    (net (code "61") (name "/MX2") (class "Default")
      (node (ref "T2") (pin "P$16") (pinfunction "MX1_P$16") (pintype "bidirectional"))
      (node (ref "T3") (pin "W6") (pinfunction "P$56_W6") (pintype "bidirectional"))
    )
    (net (code "62") (name "/MX3") (class "Default")
      (node (ref "T2") (pin "P$17") (pinfunction "MX0_P$17") (pintype "bidirectional"))
      (node (ref "T3") (pin "W30") (pinfunction "P$80_W30") (pintype "bidirectional"))
    )
    (net (code "63") (name "/MX4") (class "Default")
      (node (ref "T1") (pin "P$17") (pinfunction "MX0_P$17") (pintype "bidirectional"))
      (node (ref "T3") (pin "W21") (pinfunction "P$71_W21") (pintype "bidirectional"))
    )
    (net (code "64") (name "/MX5") (class "Default")
      (node (ref "T1") (pin "P$16") (pinfunction "MX1_P$16") (pintype "bidirectional"))
      (node (ref "T3") (pin "W46") (pinfunction "P$96_W46") (pintype "bidirectional"))
    )
    (net (code "65") (name "/MX6") (class "Default")
      (node (ref "T1") (pin "P$42") (pinfunction "RSV_P$42") (pintype "bidirectional"))
      (node (ref "T3") (pin "W45") (pinfunction "P$95_W45") (pintype "bidirectional"))
    )
    (net (code "66") (name "/MX7") (class "Default")
      (node (ref "T3") (pin "E5") (pinfunction "P$5_E5") (pintype "bidirectional"))
      (node (ref "T5") (pin "P$42") (pinfunction "RSV_P$42") (pintype "bidirectional"))
    )
    (net (code "67") (name "/MX8") (class "Default")
      (node (ref "T3") (pin "E6") (pinfunction "P$6_E6") (pintype "bidirectional"))
      (node (ref "T5") (pin "P$16") (pinfunction "MX1_P$16") (pintype "bidirectional"))
    )
    (net (code "68") (name "/MX9") (class "Default")
      (node (ref "T3") (pin "E30") (pinfunction "P$30_E30") (pintype "bidirectional"))
      (node (ref "T5") (pin "P$17") (pinfunction "MX0_P$17") (pintype "bidirectional"))
    )
    (net (code "69") (name "/MX10") (class "Default")
      (node (ref "T3") (pin "E21") (pinfunction "P$21_E21") (pintype "bidirectional"))
      (node (ref "T4") (pin "P$17") (pinfunction "MX0_P$17") (pintype "bidirectional"))
    )
    (net (code "70") (name "/MX11") (class "Default")
      (node (ref "T3") (pin "E46") (pinfunction "P$46_E46") (pintype "bidirectional"))
      (node (ref "T4") (pin "P$16") (pinfunction "MX1_P$16") (pintype "bidirectional"))
    )
    (net (code "71") (name "/MX12") (class "Default")
      (node (ref "T3") (pin "E45") (pinfunction "P$45_E45") (pintype "bidirectional"))
      (node (ref "T4") (pin "P$42") (pinfunction "RSV_P$42") (pintype "bidirectional"))
    )
    (net (code "72") (name "/N$1") (class "Default")
      (node (ref "C34") (pin "2") (pinfunction "2_2") (pintype "passive"))
      (node (ref "D3") (pin "A") (pinfunction "A_A") (pintype "passive"))
      (node (ref "IC10") (pin "12") (pinfunction "VCONN_1_12") (pintype "bidirectional"))
      (node (ref "IC10") (pin "13") (pinfunction "VCONN_2_13") (pintype "bidirectional"))
    )
    (net (code "73") (name "/PEN") (class "Default")
      (node (ref "C5") (pin "1") (pinfunction "1_1") (pintype "passive"))
      (node (ref "IC1") (pin "1") (pinfunction "EN_1") (pintype "input"))
      (node (ref "RN1") (pin "8") (pinfunction "2_8") (pintype "passive"))
    )
    (net (code "74") (name "/PRT") (class "Default")
      (node (ref "IC3") (pin "L9") (pinfunction "CRESET_B_L9") (pintype "bidirectional"))
      (node (ref "T3") (pin "E38") (pinfunction "P$38_E38") (pintype "bidirectional"))
    )
    (net (code "75") (name "/RESET") (class "Default")
      (node (ref "T1") (pin "P$15") (pinfunction "PRG/RS_P$15") (pintype "open_collector"))
      (node (ref "T2") (pin "P$15") (pinfunction "PRG/RS_P$15") (pintype "open_collector"))
      (node (ref "T4") (pin "P$15") (pinfunction "PRG/RS_P$15") (pintype "open_collector"))
      (node (ref "T5") (pin "P$15") (pinfunction "PRG/RS_P$15") (pintype "open_collector"))
    )
    (net (code "76") (name "/SCK") (class "Default")
      (node (ref "RN11") (pin "3") (pinfunction "1_3") (pintype "passive"))
      (node (ref "T3") (pin "W33") (pinfunction "P$83_W33") (pintype "bidirectional"))
    )
    (net (code "77") (name "/SCL") (class "Default")
      (node (ref "IC10") (pin "6") (pinfunction "SCL_6") (pintype "bidirectional"))
      (node (ref "RN27") (pin "7") (pinfunction "2_7") (pintype "passive"))
      (node (ref "T2") (pin "P$39") (pinfunction "ICL_P$39") (pintype "bidirectional"))
      (node (ref "T3") (pin "E32") (pinfunction "P$32_E32") (pintype "bidirectional"))
      (node (ref "T5") (pin "P$39") (pinfunction "ICL_P$39") (pintype "bidirectional"))
    )
    (net (code "78") (name "/SCL2") (class "Default")
      (node (ref "RN27") (pin "5") (pinfunction "2_5") (pintype "passive"))
      (node (ref "T1") (pin "P$39") (pinfunction "ICL_P$39") (pintype "bidirectional"))
      (node (ref "T3") (pin "E44") (pinfunction "P$44_E44") (pintype "bidirectional"))
      (node (ref "T4") (pin "P$39") (pinfunction "ICL_P$39") (pintype "bidirectional"))
    )
    (net (code "79") (name "/SDA") (class "Default")
      (node (ref "IC10") (pin "7") (pinfunction "SDA_7") (pintype "bidirectional"))
      (node (ref "RN27") (pin "8") (pinfunction "2_8") (pintype "passive"))
      (node (ref "T2") (pin "P$14") (pinfunction "IDA_P$14") (pintype "bidirectional"))
      (node (ref "T3") (pin "E7") (pinfunction "P$7_E7") (pintype "bidirectional"))
      (node (ref "T5") (pin "P$14") (pinfunction "IDA_P$14") (pintype "bidirectional"))
    )
    (net (code "80") (name "/SDA2") (class "Default")
      (node (ref "RN27") (pin "6") (pinfunction "2_6") (pintype "passive"))
      (node (ref "T1") (pin "P$14") (pinfunction "IDA_P$14") (pintype "bidirectional"))
      (node (ref "T3") (pin "E19") (pinfunction "P$19_E19") (pintype "bidirectional"))
      (node (ref "T4") (pin "P$14") (pinfunction "IDA_P$14") (pintype "bidirectional"))
    )
    (net (code "81") (name "/SI") (class "Default")
      (node (ref "RN11") (pin "2") (pinfunction "1_2") (pintype "passive"))
      (node (ref "T3") (pin "W9") (pinfunction "P$59_W9") (pintype "bidirectional"))
    )
    (net (code "82") (name "/SO") (class "Default")
      (node (ref "RN11") (pin "1") (pinfunction "1_1") (pintype "passive"))
      (node (ref "T3") (pin "W34") (pinfunction "P$84_W34") (pintype "bidirectional"))
    )
    (net (code "83") (name "/TB0") (class "Default")
      (node (ref "IC3") (pin "B1") (pinfunction "IOL_2A_B1") (pintype "bidirectional"))
      (node (ref "RN23") (pin "3") (pinfunction "1_3") (pintype "passive"))
    )
    (net (code "84") (name "/TB1") (class "Default")
      (node (ref "IC3") (pin "B2") (pinfunction "IOL_2B_B2") (pintype "bidirectional"))
      (node (ref "RN23") (pin "4") (pinfunction "1_4") (pintype "passive"))
    )
    (net (code "85") (name "/TB2") (class "Default")
      (node (ref "IC3") (pin "C4") (pinfunction "IOL_4A_C4") (pintype "bidirectional"))
      (node (ref "RN23") (pin "1") (pinfunction "1_1") (pintype "passive"))
    )
    (net (code "86") (name "/TB3") (class "Default")
      (node (ref "IC3") (pin "C3") (pinfunction "IOL_4B_C3") (pintype "bidirectional"))
      (node (ref "RN23") (pin "2") (pinfunction "1_2") (pintype "passive"))
    )
    (net (code "87") (name "/TB4") (class "Default")
      (node (ref "IC3") (pin "C2") (pinfunction "IOL_5A_C2") (pintype "bidirectional"))
      (node (ref "RN22") (pin "3") (pinfunction "1_3") (pintype "passive"))
    )
    (net (code "88") (name "/TB5") (class "Default")
      (node (ref "IC3") (pin "C1") (pinfunction "IOL_5B_C1") (pintype "bidirectional"))
      (node (ref "RN22") (pin "4") (pinfunction "1_4") (pintype "passive"))
    )
    (net (code "89") (name "/TB6") (class "Default")
      (node (ref "IC3") (pin "E1") (pinfunction "IOL_8A_E1") (pintype "bidirectional"))
      (node (ref "RN22") (pin "1") (pinfunction "1_1") (pintype "passive"))
    )
    (net (code "90") (name "/TB7") (class "Default")
      (node (ref "IC3") (pin "D1") (pinfunction "IOL_8B_D1") (pintype "bidirectional"))
      (node (ref "RN22") (pin "2") (pinfunction "1_2") (pintype "passive"))
    )
    (net (code "91") (name "/TB8") (class "Default")
      (node (ref "IC3") (pin "D2") (pinfunction "IOL_9A_D2") (pintype "bidirectional"))
      (node (ref "RN21") (pin "3") (pinfunction "1_3") (pintype "passive"))
    )
    (net (code "92") (name "/TB9") (class "Default")
      (node (ref "IC3") (pin "D3") (pinfunction "IOL_9B_D3") (pintype "bidirectional"))
      (node (ref "RN21") (pin "4") (pinfunction "1_4") (pintype "passive"))
    )
    (net (code "93") (name "/TB10") (class "Default")
      (node (ref "IC3") (pin "E2") (pinfunction "IOL_10A_E2") (pintype "bidirectional"))
      (node (ref "RN21") (pin "1") (pinfunction "1_1") (pintype "passive"))
    )
    (net (code "94") (name "/TB11") (class "Default")
      (node (ref "IC3") (pin "E3") (pinfunction "IOL_10B_E3") (pintype "bidirectional"))
      (node (ref "RN21") (pin "2") (pinfunction "1_2") (pintype "passive"))
    )
    (net (code "95") (name "/TC0") (class "Default")
      (node (ref "IC3") (pin "F1") (pinfunction "IOL_12A_F1") (pintype "bidirectional"))
      (node (ref "RN17") (pin "3") (pinfunction "1_3") (pintype "passive"))
    )
    (net (code "96") (name "/TC1") (class "Default")
      (node (ref "IC3") (pin "F2") (pinfunction "IOL_12B_F2") (pintype "bidirectional"))
      (node (ref "RN17") (pin "4") (pinfunction "1_4") (pintype "passive"))
    )
    (net (code "97") (name "/TC2") (class "Default")
      (node (ref "IC3") (pin "F4") (pinfunction "IOL_13A_F4") (pintype "bidirectional"))
      (node (ref "RN17") (pin "1") (pinfunction "1_1") (pintype "passive"))
    )
    (net (code "98") (name "/TC3") (class "Default")
      (node (ref "IC3") (pin "F3") (pinfunction "IOL_13B_GBIN7_F3") (pintype "bidirectional"))
      (node (ref "RN17") (pin "2") (pinfunction "1_2") (pintype "passive"))
    )
    (net (code "99") (name "/TC4") (class "Default")
      (node (ref "IC3") (pin "G1") (pinfunction "IOL_14A_GBIN6_G1") (pintype "bidirectional"))
      (node (ref "RN16") (pin "3") (pinfunction "1_3") (pintype "passive"))
    )
    (net (code "100") (name "/TC5") (class "Default")
      (node (ref "IC3") (pin "G2") (pinfunction "IOL_14B_G2") (pintype "bidirectional"))
      (node (ref "RN16") (pin "4") (pinfunction "1_4") (pintype "passive"))
    )
    (net (code "101") (name "/TC6") (class "Default")
      (node (ref "IC3") (pin "G3") (pinfunction "IOL_17A_G3") (pintype "bidirectional"))
      (node (ref "RN16") (pin "1") (pinfunction "1_1") (pintype "passive"))
    )
    (net (code "102") (name "/TC7") (class "Default")
      (node (ref "IC3") (pin "H3") (pinfunction "IOL_17B_H3") (pintype "bidirectional"))
      (node (ref "RN16") (pin "2") (pinfunction "1_2") (pintype "passive"))
    )
    (net (code "103") (name "/TC8") (class "Default")
      (node (ref "IC3") (pin "H1") (pinfunction "IOL_18A_H1") (pintype "bidirectional"))
      (node (ref "RN15") (pin "3") (pinfunction "1_3") (pintype "passive"))
    )
    (net (code "104") (name "/TC9") (class "Default")
      (node (ref "IC3") (pin "H2") (pinfunction "IOL_18B_H2") (pintype "bidirectional"))
      (node (ref "RN15") (pin "2") (pinfunction "1_2") (pintype "passive"))
    )
    (net (code "105") (name "/TC10") (class "Default")
      (node (ref "IC3") (pin "J1") (pinfunction "IOL_23A_J1") (pintype "bidirectional"))
      (node (ref "RN15") (pin "1") (pinfunction "1_1") (pintype "passive"))
    )
    (net (code "106") (name "/TC11") (class "Default")
      (node (ref "IC3") (pin "K1") (pinfunction "IOL_23B_K1") (pintype "bidirectional"))
      (node (ref "RN15") (pin "4") (pinfunction "1_4") (pintype "passive"))
    )
    (net (code "107") (name "/TF0") (class "Default")
      (node (ref "IC3") (pin "A9") (pinfunction "IOT_178A_A9") (pintype "bidirectional"))
      (node (ref "RN26") (pin "8") (pinfunction "2_8") (pintype "passive"))
    )
    (net (code "108") (name "/TF1") (class "Default")
      (node (ref "IC3") (pin "C8") (pinfunction "IOT_179B_C8") (pintype "bidirectional"))
      (node (ref "RN26") (pin "7") (pinfunction "2_7") (pintype "passive"))
    )
    (net (code "109") (name "/TF2") (class "Default")
      (node (ref "IC3") (pin "A8") (pinfunction "IOT_190A_A8") (pintype "bidirectional"))
      (node (ref "RN26") (pin "6") (pinfunction "2_6") (pintype "passive"))
    )
    (net (code "110") (name "/TF3") (class "Default")
      (node (ref "IC3") (pin "C7") (pinfunction "IOT_191B_C7") (pintype "bidirectional"))
      (node (ref "RN26") (pin "5") (pinfunction "2_5") (pintype "passive"))
    )
    (net (code "111") (name "/TF4") (class "Default")
      (node (ref "IC3") (pin "A6") (pinfunction "IOT_206A_A6") (pintype "bidirectional"))
      (node (ref "RN25") (pin "8") (pinfunction "2_8") (pintype "passive"))
    )
    (net (code "112") (name "/TF5") (class "Default")
      (node (ref "IC3") (pin "A5") (pinfunction "IOT_207B_A5") (pintype "bidirectional"))
      (node (ref "RN25") (pin "7") (pinfunction "2_7") (pintype "passive"))
    )
    (net (code "113") (name "/TF6") (class "Default")
      (node (ref "IC3") (pin "A2") (pinfunction "IOT_222A_A2") (pintype "bidirectional"))
      (node (ref "RN25") (pin "6") (pinfunction "2_6") (pintype "passive"))
    )
    (net (code "114") (name "/TF7") (class "Default")
      (node (ref "IC3") (pin "A3") (pinfunction "IOT_223B_A3") (pintype "bidirectional"))
      (node (ref "RN25") (pin "5") (pinfunction "2_5") (pintype "passive"))
    )
    (net (code "115") (name "/TF8") (class "Default")
      (node (ref "IC3") (pin "F11") (pinfunction "IOR_140_GBIN3_F11") (pintype "bidirectional"))
      (node (ref "RN24") (pin "8") (pinfunction "2_8") (pintype "passive"))
    )
    (net (code "116") (name "/TF9") (class "Default")
      (node (ref "IC3") (pin "E9") (pinfunction "IOR_144_E9") (pintype "bidirectional"))
      (node (ref "RN24") (pin "7") (pinfunction "2_7") (pintype "passive"))
    )
    (net (code "117") (name "/TF10") (class "Default")
      (node (ref "IC3") (pin "E10") (pinfunction "IOR_141_GBIN2_E10") (pintype "bidirectional"))
      (node (ref "RN24") (pin "6") (pinfunction "2_6") (pintype "passive"))
    )
    (net (code "118") (name "/TF11") (class "Default")
      (node (ref "IC3") (pin "E8") (pinfunction "IOR_146_E8") (pintype "bidirectional"))
      (node (ref "RN24") (pin "5") (pinfunction "2_5") (pintype "passive"))
    )
    (net (code "119") (name "/TG0") (class "Default")
      (node (ref "IC3") (pin "K11") (pinfunction "IOR_115A_K11") (pintype "bidirectional"))
      (node (ref "RN20") (pin "8") (pinfunction "2_8") (pintype "passive"))
    )
    (net (code "120") (name "/TG1") (class "Default")
      (node (ref "IC3") (pin "H10") (pinfunction "IOR_116B_H10") (pintype "bidirectional"))
      (node (ref "RN20") (pin "7") (pinfunction "2_7") (pintype "passive"))
    )
    (net (code "121") (name "/TG2") (class "Default")
      (node (ref "IC3") (pin "J10") (pinfunction "IOR_117A_J10") (pintype "bidirectional"))
      (node (ref "RN20") (pin "6") (pinfunction "2_6") (pintype "passive"))
    )
    (net (code "122") (name "/TG3") (class "Default")
      (node (ref "IC3") (pin "G8") (pinfunction "IOR_118B_G8") (pintype "bidirectional"))
      (node (ref "RN20") (pin "5") (pinfunction "2_5") (pintype "passive"))
    )
    (net (code "123") (name "/TG4") (class "Default")
      (node (ref "IC3") (pin "H11") (pinfunction "IOR_119A_H11") (pintype "bidirectional"))
      (node (ref "RN19") (pin "8") (pinfunction "2_8") (pintype "passive"))
    )
    (net (code "124") (name "/TG5") (class "Default")
      (node (ref "IC3") (pin "G10") (pinfunction "IOR_120B_G10") (pintype "bidirectional"))
      (node (ref "RN19") (pin "7") (pinfunction "2_7") (pintype "passive"))
    )
    (net (code "125") (name "/TG6") (class "Default")
      (node (ref "IC3") (pin "D9") (pinfunction "IOR_147A_D9") (pintype "bidirectional"))
      (node (ref "RN19") (pin "6") (pinfunction "2_6") (pintype "passive"))
    )
    (net (code "126") (name "/TG7") (class "Default")
      (node (ref "IC3") (pin "E11") (pinfunction "IOR_148B_E11") (pintype "bidirectional"))
      (node (ref "RN19") (pin "5") (pinfunction "2_5") (pintype "passive"))
    )
    (net (code "127") (name "/TG8") (class "Default")
      (node (ref "IC3") (pin "G9") (pinfunction "IOR_128_G9") (pintype "bidirectional"))
      (node (ref "RN18") (pin "8") (pinfunction "2_8") (pintype "passive"))
    )
    (net (code "128") (name "/TG9") (class "Default")
      (node (ref "IC3") (pin "G11") (pinfunction "IOR_129_G11") (pintype "bidirectional"))
      (node (ref "RN18") (pin "7") (pinfunction "2_7") (pintype "passive"))
    )
    (net (code "129") (name "/TG10") (class "Default")
      (node (ref "IC3") (pin "F10") (pinfunction "IOR_136_F10") (pintype "bidirectional"))
      (node (ref "RN18") (pin "6") (pinfunction "2_6") (pintype "passive"))
    )
    (net (code "130") (name "/TG11") (class "Default")
      (node (ref "IC3") (pin "F9") (pinfunction "IOR_137_F9") (pintype "bidirectional"))
      (node (ref "RN18") (pin "5") (pinfunction "2_5") (pintype "passive"))
    )
    (net (code "131") (name "/VB1+") (class "Default")
      (node (ref "D2") (pin "C") (pinfunction "C_C") (pintype "passive"))
      (node (ref "T1") (pin "P$20") (pinfunction "V+_P$20") (pintype "power_in"))
      (node (ref "T1") (pin "P$21") (pinfunction "V+_P$21") (pintype "power_in"))
      (node (ref "T1") (pin "P$22") (pinfunction "V+_P$22") (pintype "power_in"))
      (node (ref "T1") (pin "P$23") (pinfunction "V+_P$23") (pintype "power_in"))
      (node (ref "T1") (pin "P$24") (pinfunction "V+_P$24") (pintype "power_in"))
      (node (ref "T1") (pin "P$25") (pinfunction "V+_P$25") (pintype "power_in"))
      (node (ref "T1") (pin "P$45") (pinfunction "V+_P$45") (pintype "power_in"))
      (node (ref "T1") (pin "P$46") (pinfunction "V+_P$46") (pintype "power_in"))
      (node (ref "T1") (pin "P$47") (pinfunction "V+_P$47") (pintype "power_in"))
      (node (ref "T1") (pin "P$48") (pinfunction "V+_P$48") (pintype "power_in"))
      (node (ref "T1") (pin "P$49") (pinfunction "V+_P$49") (pintype "power_in"))
      (node (ref "T1") (pin "P$50") (pinfunction "V+_P$50") (pintype "power_in"))
      (node (ref "T3") (pin "E23") (pinfunction "P$23_E23") (pintype "bidirectional"))
      (node (ref "T3") (pin "E24") (pinfunction "P$24_E24") (pintype "bidirectional"))
      (node (ref "T3") (pin "E25") (pinfunction "P$25_E25") (pintype "bidirectional"))
      (node (ref "T3") (pin "W22") (pinfunction "P$72_W22") (pintype "bidirectional"))
      (node (ref "T3") (pin "W23") (pinfunction "P$73_W23") (pintype "bidirectional"))
      (node (ref "T3") (pin "W24") (pinfunction "P$74_W24") (pintype "bidirectional"))
      (node (ref "T3") (pin "W25") (pinfunction "P$75_W25") (pintype "bidirectional"))
      (node (ref "T4") (pin "P$20") (pinfunction "V+_P$20") (pintype "power_in"))
      (node (ref "T4") (pin "P$21") (pinfunction "V+_P$21") (pintype "power_in"))
      (node (ref "T4") (pin "P$22") (pinfunction "V+_P$22") (pintype "power_in"))
      (node (ref "T4") (pin "P$23") (pinfunction "V+_P$23") (pintype "power_in"))
      (node (ref "T4") (pin "P$24") (pinfunction "V+_P$24") (pintype "power_in"))
      (node (ref "T4") (pin "P$25") (pinfunction "V+_P$25") (pintype "power_in"))
      (node (ref "T4") (pin "P$45") (pinfunction "V+_P$45") (pintype "power_in"))
      (node (ref "T4") (pin "P$46") (pinfunction "V+_P$46") (pintype "power_in"))
      (node (ref "T4") (pin "P$47") (pinfunction "V+_P$47") (pintype "power_in"))
      (node (ref "T4") (pin "P$48") (pinfunction "V+_P$48") (pintype "power_in"))
      (node (ref "T4") (pin "P$49") (pinfunction "V+_P$49") (pintype "power_in"))
      (node (ref "T4") (pin "P$50") (pinfunction "V+_P$50") (pintype "power_in"))
    )
    (net (code "132") (name "/VB2+") (class "Default")
      (node (ref "D1") (pin "C") (pinfunction "C_C") (pintype "passive"))
      (node (ref "T2") (pin "P$20") (pinfunction "V+_P$20") (pintype "power_in"))
      (node (ref "T2") (pin "P$21") (pinfunction "V+_P$21") (pintype "power_in"))
      (node (ref "T2") (pin "P$22") (pinfunction "V+_P$22") (pintype "power_in"))
      (node (ref "T2") (pin "P$23") (pinfunction "V+_P$23") (pintype "power_in"))
      (node (ref "T2") (pin "P$24") (pinfunction "V+_P$24") (pintype "power_in"))
      (node (ref "T2") (pin "P$25") (pinfunction "V+_P$25") (pintype "power_in"))
      (node (ref "T2") (pin "P$45") (pinfunction "V+_P$45") (pintype "power_in"))
      (node (ref "T2") (pin "P$46") (pinfunction "V+_P$46") (pintype "power_in"))
      (node (ref "T2") (pin "P$47") (pinfunction "V+_P$47") (pintype "power_in"))
      (node (ref "T2") (pin "P$48") (pinfunction "V+_P$48") (pintype "power_in"))
      (node (ref "T2") (pin "P$49") (pinfunction "V+_P$49") (pintype "power_in"))
      (node (ref "T2") (pin "P$50") (pinfunction "V+_P$50") (pintype "power_in"))
      (node (ref "T3") (pin "E26") (pinfunction "P$26_E26") (pintype "bidirectional"))
      (node (ref "T3") (pin "E27") (pinfunction "P$27_E27") (pintype "bidirectional"))
      (node (ref "T3") (pin "E28") (pinfunction "P$28_E28") (pintype "bidirectional"))
      (node (ref "T3") (pin "W26") (pinfunction "P$76_W26") (pintype "bidirectional"))
      (node (ref "T3") (pin "W27") (pinfunction "P$77_W27") (pintype "bidirectional"))
      (node (ref "T3") (pin "W28") (pinfunction "P$78_W28") (pintype "bidirectional"))
      (node (ref "T3") (pin "W29") (pinfunction "P$79_W29") (pintype "bidirectional"))
      (node (ref "T5") (pin "P$20") (pinfunction "V+_P$20") (pintype "power_in"))
      (node (ref "T5") (pin "P$21") (pinfunction "V+_P$21") (pintype "power_in"))
      (node (ref "T5") (pin "P$22") (pinfunction "V+_P$22") (pintype "power_in"))
      (node (ref "T5") (pin "P$23") (pinfunction "V+_P$23") (pintype "power_in"))
      (node (ref "T5") (pin "P$24") (pinfunction "V+_P$24") (pintype "power_in"))
      (node (ref "T5") (pin "P$25") (pinfunction "V+_P$25") (pintype "power_in"))
      (node (ref "T5") (pin "P$45") (pinfunction "V+_P$45") (pintype "power_in"))
      (node (ref "T5") (pin "P$46") (pinfunction "V+_P$46") (pintype "power_in"))
      (node (ref "T5") (pin "P$47") (pinfunction "V+_P$47") (pintype "power_in"))
      (node (ref "T5") (pin "P$48") (pinfunction "V+_P$48") (pintype "power_in"))
      (node (ref "T5") (pin "P$49") (pinfunction "V+_P$49") (pintype "power_in"))
      (node (ref "T5") (pin "P$50") (pinfunction "V+_P$50") (pintype "power_in"))
    )
    (net (code "133") (name "/VBUS") (class "Default")
      (node (ref "D1") (pin "A") (pinfunction "A_A") (pintype "passive"))
      (node (ref "D2") (pin "A") (pinfunction "A_A") (pintype "passive"))
      (node (ref "IC10") (pin "2") (pinfunction "VBUS_2") (pintype "bidirectional"))
      (node (ref "U$1") (pin "VBUS@1") (pinfunction "VBUS_VBUS@1") (pintype "power_in"))
      (node (ref "U$1") (pin "VBUS@2") (pinfunction "VBUS_VBUS@2") (pintype "power_in"))
      (node (ref "U$2") (pin "P$2") (pinfunction "V+_P$2") (pintype "power_in"))
    )
    (net (code "134") (name "/VCC") (class "Default")
      (node (ref "C10") (pin "1") (pinfunction "1_1") (pintype "passive"))
      (node (ref "C18") (pin "2") (pinfunction "2_2") (pintype "passive"))
      (node (ref "C21") (pin "2") (pinfunction "2_2") (pintype "passive"))
      (node (ref "C24") (pin "2") (pinfunction "2_2") (pintype "passive"))
      (node (ref "C6") (pin "2") (pinfunction "2_2") (pintype "passive"))
      (node (ref "IC3") (pin "D4") (pinfunction "VCC_1_D4") (pintype "bidirectional"))
      (node (ref "IC3") (pin "D8") (pinfunction "VCC_2_D8") (pintype "bidirectional"))
      (node (ref "IC3") (pin "H4") (pinfunction "VCC_3_H4") (pintype "bidirectional"))
      (node (ref "IC3") (pin "H8") (pinfunction "VCC_4_H8") (pintype "bidirectional"))
      (node (ref "L1") (pin "P$2") (pinfunction "P$2_P$2") (pintype "passive"))
      (node (ref "R1") (pin "1") (pinfunction "1_1") (pintype "passive"))
      (node (ref "R2") (pin "2") (pinfunction "2_2") (pintype "passive"))
      (node (ref "RN8") (pin "8") (pinfunction "2_8") (pintype "passive"))
      (node (ref "T3") (pin "E4") (pinfunction "P$4_E4") (pintype "bidirectional"))
    )
    (net (code "135") (name "/VPLL0") (class "Default")
      (node (ref "C8") (pin "2") (pinfunction "2_2") (pintype "passive"))
      (node (ref "C9") (pin "2") (pinfunction "2_2") (pintype "passive"))
      (node (ref "IC3") (pin "J6") (pinfunction "VCCPLL0_J6") (pintype "bidirectional"))
      (node (ref "R2") (pin "1") (pinfunction "1_1") (pintype "passive"))
    )
    (net (code "136") (name "/VPLL1") (class "Default")
      (node (ref "C3") (pin "2") (pinfunction "2_2") (pintype "passive"))
      (node (ref "C4") (pin "2") (pinfunction "2_2") (pintype "passive"))
      (node (ref "IC3") (pin "C6") (pinfunction "VCCPLL1_C6") (pintype "bidirectional"))
      (node (ref "R1") (pin "2") (pinfunction "2_2") (pintype "passive"))
    )
    (net (code "137") (name "/~HB") (class "Default")
      (node (ref "IC3") (pin "L5") (pinfunction "*IOB_81_GBIN5_L5") (pintype "bidirectional"))
      (node (ref "RN12") (pin "8") (pinfunction "2_8") (pintype "passive"))
    )
    (net (code "138") (name "/~INT") (class "Default")
      (node (ref "IC3") (pin "J11") (pinfunction "IOR_114_J11") (pintype "bidirectional"))
      (node (ref "RN14") (pin "7") (pinfunction "2_7") (pintype "passive"))
    )
    (net (code "139") (name "/~LB") (class "Default")
      (node (ref "IC3") (pin "K6") (pinfunction "IOB_82_GBIN4_K6") (pintype "bidirectional"))
      (node (ref "RN12") (pin "7") (pinfunction "2_7") (pintype "passive"))
    )
    (net (code "140") (name "/~OE") (class "Default")
      (node (ref "IC3") (pin "B6") (pinfunction "IOT_198_GBIN0_B6") (pintype "bidirectional"))
      (node (ref "RN4") (pin "6") (pinfunction "2_6") (pintype "passive"))
    )
    (net (code "141") (name "/~SS") (class "Default")
      (node (ref "IC3") (pin "K10") (pinfunction "IOB_108_SS_K10") (pintype "bidirectional"))
      (node (ref "RN11") (pin "5") (pinfunction "2_5") (pintype "passive"))
    )
    (net (code "142") (name "/~WE") (class "Default")
      (node (ref "IC3") (pin "D7") (pinfunction "IOT_181_D7") (pintype "bidirectional"))
      (node (ref "RN4") (pin "5") (pinfunction "2_5") (pintype "passive"))
    )
    (net (code "143") (name "/~{A4}") (class "Default")
      (node (ref "IC3") (pin "J7") (pinfunction "**IOB_86_J7") (pintype "bidirectional"))
      (node (ref "RN13") (pin "8") (pinfunction "2_8") (pintype "passive"))
    )
    (net (code "144") (name "/~{A5}") (class "Default")
      (node (ref "IC3") (pin "H7") (pinfunction "IOB_87_H7") (pintype "bidirectional"))
      (node (ref "RN13") (pin "7") (pinfunction "2_7") (pintype "passive"))
    )
    (net (code "145") (name "/~{A6}") (class "Default")
      (node (ref "IC3") (pin "K7") (pinfunction "IOB_89_K7") (pintype "bidirectional"))
      (node (ref "RN12") (pin "6") (pinfunction "2_6") (pintype "passive"))
    )
    (net (code "146") (name "/~{A7}") (class "Default")
      (node (ref "IC3") (pin "J8") (pinfunction "IOB_91_J8") (pintype "bidirectional"))
      (node (ref "RN13") (pin "5") (pinfunction "2_5") (pintype "passive"))
    )
    (net (code "147") (name "/~{A8}") (class "Default")
      (node (ref "IC3") (pin "L7") (pinfunction "IOB_94_L7") (pintype "bidirectional"))
      (node (ref "RN12") (pin "5") (pinfunction "2_5") (pintype "passive"))
    )
    (net (code "148") (name "/~{A9}") (class "Default")
      (node (ref "IC3") (pin "L8") (pinfunction "IOB_103_CBSEL0_L8") (pintype "bidirectional"))
      (node (ref "RN13") (pin "6") (pinfunction "2_6") (pintype "passive"))
    )
    (net (code "149") (name "/~{A10}") (class "Default")
      (node (ref "IC3") (pin "H9") (pinfunction "IOB_104_CBSEL1_H9") (pintype "bidirectional"))
      (node (ref "RN14") (pin "8") (pinfunction "2_8") (pintype "passive"))
    )
    (net (code "150") (name "/~{CS0}") (class "Default")
      (node (ref "RN5") (pin "3") (pinfunction "1_3") (pintype "passive"))
      (node (ref "T3") (pin "W43") (pinfunction "P$93_W43") (pintype "bidirectional"))
    )
    (net (code "151") (name "/~{CS1}") (class "Default")
      (node (ref "RN5") (pin "1") (pinfunction "1_1") (pintype "passive"))
      (node (ref "T3") (pin "W44") (pinfunction "P$94_W44") (pintype "bidirectional"))
    )
    (net (code "152") (name "/~{D0}") (class "Default")
      (node (ref "IC3") (pin "B11") (pinfunction "IOR_161_B11") (pintype "bidirectional"))
      (node (ref "RN10") (pin "5") (pinfunction "2_5") (pintype "passive"))
    )
    (net (code "153") (name "/~{D1}") (class "Default")
      (node (ref "IC3") (pin "A11") (pinfunction "IOT_168_A11") (pintype "bidirectional"))
      (node (ref "RN9") (pin "8") (pinfunction "2_8") (pintype "passive"))
    )
    (net (code "154") (name "/~{D2}") (class "Default")
      (node (ref "IC3") (pin "A10") (pinfunction "IOT_170_A10") (pintype "bidirectional"))
      (node (ref "RN9") (pin "7") (pinfunction "2_7") (pintype "passive"))
    )
    (net (code "155") (name "/~{D3}") (class "Default")
      (node (ref "IC3") (pin "B9") (pinfunction "IOT_174_B9") (pintype "bidirectional"))
      (node (ref "RN9") (pin "5") (pinfunction "2_5") (pintype "passive"))
    )
    (net (code "156") (name "/~{D4}") (class "Default")
      (node (ref "IC3") (pin "C9") (pinfunction "IOT_172_C9") (pintype "bidirectional"))
      (node (ref "RN9") (pin "6") (pinfunction "2_6") (pintype "passive"))
    )
    (net (code "157") (name "/~{D5}") (class "Default")
      (node (ref "IC3") (pin "B8") (pinfunction "IOT_177_B8") (pintype "bidirectional"))
      (node (ref "RN4") (pin "8") (pinfunction "2_8") (pintype "passive"))
    )
    (net (code "158") (name "/~{D6}") (class "Default")
      (node (ref "IC3") (pin "A7") (pinfunction "IOT_192_A7") (pintype "bidirectional"))
      (node (ref "RN4") (pin "7") (pinfunction "2_7") (pintype "passive"))
    )
    (net (code "159") (name "/~{D7}") (class "Default")
      (node (ref "IC3") (pin "B5") (pinfunction "IOT_208_B5") (pintype "bidirectional"))
      (node (ref "RN3") (pin "8") (pinfunction "2_8") (pintype "passive"))
    )
    (net (code "160") (name "/~{D8}") (class "Default")
      (node (ref "IC3") (pin "D5") (pinfunction "IOT_212_D5") (pintype "bidirectional"))
      (node (ref "RN3") (pin "7") (pinfunction "2_7") (pintype "passive"))
    )
    (net (code "161") (name "/~{D9}") (class "Default")
      (node (ref "IC3") (pin "A4") (pinfunction "IOT_211_A4") (pintype "bidirectional"))
      (node (ref "RN3") (pin "6") (pinfunction "2_6") (pintype "passive"))
    )
    (net (code "162") (name "/~{D10}") (class "Default")
      (node (ref "IC3") (pin "B4") (pinfunction "IOT_219_B4") (pintype "bidirectional"))
      (node (ref "RN3") (pin "5") (pinfunction "2_5") (pintype "passive"))
    )
    (net (code "163") (name "/~{D11}") (class "Default")
      (node (ref "IC3") (pin "B3") (pinfunction "IOT_221_B3") (pintype "bidirectional"))
      (node (ref "RN2") (pin "4") (pinfunction "1_4") (pintype "passive"))
    )
    (net (code "164") (name "/~{D12}") (class "Default")
      (node (ref "IC3") (pin "A1") (pinfunction "IOT_225_A1") (pintype "bidirectional"))
      (node (ref "RN2") (pin "3") (pinfunction "1_3") (pintype "passive"))
    )
    (net (code "165") (name "/~{D13}") (class "Default")
      (node (ref "IC3") (pin "C11") (pinfunction "IOR_160_C11") (pintype "bidirectional"))
      (node (ref "RN10") (pin "6") (pinfunction "2_6") (pintype "passive"))
    )
    (net (code "166") (name "/~{D14}") (class "Default")
      (node (ref "IC3") (pin "D10") (pinfunction "IOR_154_D10") (pintype "bidirectional"))
      (node (ref "RN10") (pin "8") (pinfunction "2_8") (pintype "passive"))
    )
    (net (code "167") (name "/~{D15}") (class "Default")
      (node (ref "IC3") (pin "D11") (pinfunction "IOR_152_D11") (pintype "bidirectional"))
      (node (ref "RN10") (pin "7") (pinfunction "2_7") (pintype "passive"))
    )
    (net (code "168") (name "/~{HB}") (class "Default")
      (node (ref "RN12") (pin "1") (pinfunction "1_1") (pintype "passive"))
      (node (ref "T3") (pin "W14") (pinfunction "P$64_W14") (pintype "bidirectional"))
    )
    (net (code "169") (name "/~{INT}") (class "Default")
      (node (ref "IC10") (pin "5") (pinfunction "INT_N_5") (pintype "bidirectional"))
      (node (ref "RN1") (pin "5") (pinfunction "2_5") (pintype "passive"))
      (node (ref "RN14") (pin "2") (pinfunction "1_2") (pintype "passive"))
      (node (ref "T3") (pin "W32") (pinfunction "P$82_W32") (pintype "bidirectional"))
    )
    (net (code "170") (name "/~{LB}") (class "Default")
      (node (ref "RN12") (pin "2") (pinfunction "1_2") (pintype "passive"))
      (node (ref "T3") (pin "W37") (pinfunction "P$87_W37") (pintype "bidirectional"))
    )
    (net (code "171") (name "/~{OE}") (class "Default")
      (node (ref "RN4") (pin "3") (pinfunction "1_3") (pintype "passive"))
      (node (ref "T3") (pin "E15") (pinfunction "P$15_E15") (pintype "bidirectional"))
    )
    (net (code "172") (name "/~{SCK}") (class "Default")
      (node (ref "IC3") (pin "L10") (pinfunction "IOB_107_SCK_L10") (pintype "bidirectional"))
      (node (ref "RN11") (pin "6") (pinfunction "2_6") (pintype "passive"))
    )
    (net (code "173") (name "/~{SI}") (class "Default")
      (node (ref "IC3") (pin "J9") (pinfunction "IOB_106_SDI_J9") (pintype "bidirectional"))
      (node (ref "RN11") (pin "7") (pinfunction "2_7") (pintype "passive"))
    )
    (net (code "174") (name "/~{SO}") (class "Default")
      (node (ref "IC3") (pin "K9") (pinfunction "IOB_105_SDO_K9") (pintype "bidirectional"))
      (node (ref "RN11") (pin "8") (pinfunction "2_8") (pintype "passive"))
    )
    (net (code "175") (name "/~{SS}") (class "Default")
      (node (ref "RN1") (pin "6") (pinfunction "2_6") (pintype "passive"))
      (node (ref "RN11") (pin "4") (pinfunction "1_4") (pintype "passive"))
      (node (ref "T3") (pin "W8") (pinfunction "P$58_W8") (pintype "bidirectional"))
    )
    (net (code "176") (name "/~{WE}") (class "Default")
      (node (ref "RN4") (pin "4") (pinfunction "1_4") (pintype "passive"))
      (node (ref "T3") (pin "E40") (pinfunction "P$40_E40") (pintype "bidirectional"))
    )
    (net (code "177") (name "GND") (class "Default")
      (node (ref "C1") (pin "1") (pinfunction "1_1") (pintype "passive"))
      (node (ref "C10") (pin "2") (pinfunction "2_2") (pintype "passive"))
      (node (ref "C11") (pin "2") (pinfunction "2_2") (pintype "passive"))
      (node (ref "C12") (pin "1") (pinfunction "1_1") (pintype "passive"))
      (node (ref "C13") (pin "2") (pinfunction "2_2") (pintype "passive"))
      (node (ref "C14") (pin "1") (pinfunction "1_1") (pintype "passive"))
      (node (ref "C15") (pin "1") (pinfunction "1_1") (pintype "passive"))
      (node (ref "C16") (pin "1") (pinfunction "1_1") (pintype "passive"))
      (node (ref "C17") (pin "2") (pinfunction "2_2") (pintype "passive"))
      (node (ref "C18") (pin "1") (pinfunction "1_1") (pintype "passive"))
      (node (ref "C19") (pin "1") (pinfunction "1_1") (pintype "passive"))
      (node (ref "C2") (pin "1") (pinfunction "1_1") (pintype "passive"))
      (node (ref "C20") (pin "2") (pinfunction "2_2") (pintype "passive"))
      (node (ref "C21") (pin "1") (pinfunction "1_1") (pintype "passive"))
      (node (ref "C22") (pin "1") (pinfunction "1_1") (pintype "passive"))
      (node (ref "C23") (pin "2") (pinfunction "2_2") (pintype "passive"))
      (node (ref "C24") (pin "1") (pinfunction "1_1") (pintype "passive"))
      (node (ref "C25") (pin "1") (pinfunction "1_1") (pintype "passive"))
      (node (ref "C31") (pin "1") (pinfunction "1_1") (pintype "passive"))
      (node (ref "C32") (pin "1") (pinfunction "1_1") (pintype "passive"))
      (node (ref "C33") (pin "2") (pinfunction "2_2") (pintype "passive"))
      (node (ref "C34") (pin "1") (pinfunction "1_1") (pintype "passive"))
      (node (ref "C5") (pin "2") (pinfunction "2_2") (pintype "passive"))
      (node (ref "IC1") (pin "2") (pinfunction "GND_2") (pintype "power_in"))
      (node (ref "IC10") (pin "8") (pinfunction "GND_1_8") (pintype "bidirectional"))
      (node (ref "IC10") (pin "9") (pinfunction "GND_2_9") (pintype "bidirectional"))
      (node (ref "IC2") (pin "2") (pinfunction "GND_2") (pintype "power_in"))
      (node (ref "IC3") (pin "E5") (pinfunction "GND_1_E5") (pintype "bidirectional"))
      (node (ref "IC3") (pin "E6") (pinfunction "GND_2_E6") (pintype "bidirectional"))
      (node (ref "IC3") (pin "E7") (pinfunction "GND_3_E7") (pintype "bidirectional"))
      (node (ref "IC3") (pin "F5") (pinfunction "GND_4_F5") (pintype "bidirectional"))
      (node (ref "IC3") (pin "F6") (pinfunction "GND_5_F6") (pintype "bidirectional"))
      (node (ref "IC3") (pin "F7") (pinfunction "GND_6_F7") (pintype "bidirectional"))
      (node (ref "IC3") (pin "G5") (pinfunction "GND_7_G5") (pintype "bidirectional"))
      (node (ref "IC3") (pin "G6") (pinfunction "GND_8_G6") (pintype "bidirectional"))
      (node (ref "IC3") (pin "G7") (pinfunction "GND_9_G7") (pintype "bidirectional"))
      (node (ref "IC3") (pin "H5") (pinfunction "GND_10_H5") (pintype "bidirectional"))
      (node (ref "R3") (pin "2") (pinfunction "2_2") (pintype "passive"))
      (node (ref "RN8") (pin "2") (pinfunction "1_2") (pintype "passive"))
      (node (ref "T1") (pin "0V@1") (pinfunction "0V_0V@1") (pintype "power_in"))
      (node (ref "T1") (pin "0V@2") (pinfunction "0V_0V@2") (pintype "power_in"))
      (node (ref "T1") (pin "P$1") (pinfunction "V-_P$1") (pintype "power_in"))
      (node (ref "T1") (pin "P$2") (pinfunction "V-_P$2") (pintype "power_in"))
      (node (ref "T1") (pin "P$26") (pinfunction "V-_P$26") (pintype "power_in"))
      (node (ref "T1") (pin "P$27") (pinfunction "V-_P$27") (pintype "power_in"))
      (node (ref "T1") (pin "P$28") (pinfunction "V-_P$28") (pintype "power_in"))
      (node (ref "T1") (pin "P$29") (pinfunction "V-_P$29") (pintype "power_in"))
      (node (ref "T1") (pin "P$3") (pinfunction "V-_P$3") (pintype "power_in"))
      (node (ref "T1") (pin "P$30") (pinfunction "V-_P$30") (pintype "power_in"))
      (node (ref "T1") (pin "P$31") (pinfunction "V-_P$31") (pintype "power_in"))
      (node (ref "T1") (pin "P$32") (pinfunction "GND_P$32") (pintype "power_in"))
      (node (ref "T1") (pin "P$4") (pinfunction "V-_P$4") (pintype "power_in"))
      (node (ref "T1") (pin "P$5") (pinfunction "V-_P$5") (pintype "power_in"))
      (node (ref "T1") (pin "P$6") (pinfunction "V-_P$6") (pintype "power_in"))
      (node (ref "T1") (pin "P$7") (pinfunction "GND_P$7") (pintype "power_in"))
      (node (ref "T2") (pin "0V@1") (pinfunction "0V_0V@1") (pintype "power_in"))
      (node (ref "T2") (pin "0V@2") (pinfunction "0V_0V@2") (pintype "power_in"))
      (node (ref "T2") (pin "P$1") (pinfunction "V-_P$1") (pintype "power_in"))
      (node (ref "T2") (pin "P$2") (pinfunction "V-_P$2") (pintype "power_in"))
      (node (ref "T2") (pin "P$26") (pinfunction "V-_P$26") (pintype "power_in"))
      (node (ref "T2") (pin "P$27") (pinfunction "V-_P$27") (pintype "power_in"))
      (node (ref "T2") (pin "P$28") (pinfunction "V-_P$28") (pintype "power_in"))
      (node (ref "T2") (pin "P$29") (pinfunction "V-_P$29") (pintype "power_in"))
      (node (ref "T2") (pin "P$3") (pinfunction "V-_P$3") (pintype "power_in"))
      (node (ref "T2") (pin "P$30") (pinfunction "V-_P$30") (pintype "power_in"))
      (node (ref "T2") (pin "P$31") (pinfunction "V-_P$31") (pintype "power_in"))
      (node (ref "T2") (pin "P$32") (pinfunction "GND_P$32") (pintype "power_in"))
      (node (ref "T2") (pin "P$4") (pinfunction "V-_P$4") (pintype "power_in"))
      (node (ref "T2") (pin "P$5") (pinfunction "V-_P$5") (pintype "power_in"))
      (node (ref "T2") (pin "P$6") (pinfunction "V-_P$6") (pintype "power_in"))
      (node (ref "T2") (pin "P$7") (pinfunction "GND_P$7") (pintype "power_in"))
      (node (ref "T3") (pin "E1") (pinfunction "P$1_E1") (pintype "bidirectional"))
      (node (ref "T3") (pin "E2") (pinfunction "P$2_E2") (pintype "bidirectional"))
      (node (ref "T3") (pin "E3") (pinfunction "P$3_E3") (pintype "bidirectional"))
      (node (ref "T3") (pin "E48") (pinfunction "P$48_E48") (pintype "bidirectional"))
      (node (ref "T3") (pin "E49") (pinfunction "P$49_E49") (pintype "bidirectional"))
      (node (ref "T3") (pin "E50") (pinfunction "P$50_E50") (pintype "bidirectional"))
      (node (ref "T3") (pin "W1") (pinfunction "P$51_W1") (pintype "bidirectional"))
      (node (ref "T3") (pin "W2") (pinfunction "P$52_W2") (pintype "bidirectional"))
      (node (ref "T3") (pin "W3") (pinfunction "P$53_W3") (pintype "bidirectional"))
      (node (ref "T3") (pin "W4") (pinfunction "P$54_W4") (pintype "bidirectional"))
      (node (ref "T3") (pin "W47") (pinfunction "P$97_W47") (pintype "bidirectional"))
      (node (ref "T3") (pin "W48") (pinfunction "P$98_W48") (pintype "bidirectional"))
      (node (ref "T3") (pin "W49") (pinfunction "P$99_W49") (pintype "bidirectional"))
      (node (ref "T3") (pin "W50") (pinfunction "P$100_W50") (pintype "bidirectional"))
      (node (ref "T4") (pin "0V@1") (pinfunction "0V_0V@1") (pintype "power_in"))
      (node (ref "T4") (pin "0V@2") (pinfunction "0V_0V@2") (pintype "power_in"))
      (node (ref "T4") (pin "P$1") (pinfunction "V-_P$1") (pintype "power_in"))
      (node (ref "T4") (pin "P$2") (pinfunction "V-_P$2") (pintype "power_in"))
      (node (ref "T4") (pin "P$26") (pinfunction "V-_P$26") (pintype "power_in"))
      (node (ref "T4") (pin "P$27") (pinfunction "V-_P$27") (pintype "power_in"))
      (node (ref "T4") (pin "P$28") (pinfunction "V-_P$28") (pintype "power_in"))
      (node (ref "T4") (pin "P$29") (pinfunction "V-_P$29") (pintype "power_in"))
      (node (ref "T4") (pin "P$3") (pinfunction "V-_P$3") (pintype "power_in"))
      (node (ref "T4") (pin "P$30") (pinfunction "V-_P$30") (pintype "power_in"))
      (node (ref "T4") (pin "P$31") (pinfunction "V-_P$31") (pintype "power_in"))
      (node (ref "T4") (pin "P$32") (pinfunction "GND_P$32") (pintype "power_in"))
      (node (ref "T4") (pin "P$4") (pinfunction "V-_P$4") (pintype "power_in"))
      (node (ref "T4") (pin "P$5") (pinfunction "V-_P$5") (pintype "power_in"))
      (node (ref "T4") (pin "P$6") (pinfunction "V-_P$6") (pintype "power_in"))
      (node (ref "T4") (pin "P$7") (pinfunction "GND_P$7") (pintype "power_in"))
      (node (ref "T5") (pin "0V@1") (pinfunction "0V_0V@1") (pintype "power_in"))
      (node (ref "T5") (pin "0V@2") (pinfunction "0V_0V@2") (pintype "power_in"))
      (node (ref "T5") (pin "P$1") (pinfunction "V-_P$1") (pintype "power_in"))
      (node (ref "T5") (pin "P$2") (pinfunction "V-_P$2") (pintype "power_in"))
      (node (ref "T5") (pin "P$26") (pinfunction "V-_P$26") (pintype "power_in"))
      (node (ref "T5") (pin "P$27") (pinfunction "V-_P$27") (pintype "power_in"))
      (node (ref "T5") (pin "P$28") (pinfunction "V-_P$28") (pintype "power_in"))
      (node (ref "T5") (pin "P$29") (pinfunction "V-_P$29") (pintype "power_in"))
      (node (ref "T5") (pin "P$3") (pinfunction "V-_P$3") (pintype "power_in"))
      (node (ref "T5") (pin "P$30") (pinfunction "V-_P$30") (pintype "power_in"))
      (node (ref "T5") (pin "P$31") (pinfunction "V-_P$31") (pintype "power_in"))
      (node (ref "T5") (pin "P$32") (pinfunction "GND_P$32") (pintype "power_in"))
      (node (ref "T5") (pin "P$4") (pinfunction "V-_P$4") (pintype "power_in"))
      (node (ref "T5") (pin "P$5") (pinfunction "V-_P$5") (pintype "power_in"))
      (node (ref "T5") (pin "P$6") (pinfunction "V-_P$6") (pintype "power_in"))
      (node (ref "T5") (pin "P$7") (pinfunction "GND_P$7") (pintype "power_in"))
      (node (ref "U$1") (pin "GND@1") (pinfunction "GND_GND@1") (pintype "power_in"))
      (node (ref "U$1") (pin "GND@2") (pinfunction "GND_GND@2") (pintype "power_in"))
      (node (ref "U$2") (pin "P$1") (pinfunction "V-_P$1") (pintype "power_in"))
    )
    (net (code "178") (name "Net-(C25-Pad2)") (class "Default")
      (node (ref "C25") (pin "2") (pinfunction "2_2") (pintype "passive"))
      (node (ref "U$1") (pin "P$1") (pinfunction "SHLD_P$1") (pintype "passive"))
      (node (ref "U$1") (pin "P$2") (pinfunction "SHLD_P$2") (pintype "passive"))
      (node (ref "U$1") (pin "P$3") (pinfunction "SHLD_P$3") (pintype "passive"))
      (node (ref "U$1") (pin "P$4") (pinfunction "SHLD_P$4") (pintype "passive"))
    )
    (net (code "179") (name "Net-(IC1-FB)") (class "Default")
      (node (ref "C6") (pin "1") (pinfunction "1_1") (pintype "passive"))
      (node (ref "IC1") (pin "5") (pinfunction "FB_5") (pintype "input"))
      (node (ref "RN8") (pin "1") (pinfunction "1_1") (pintype "passive"))
      (node (ref "RN8") (pin "7") (pinfunction "2_7") (pintype "passive"))
    )
    (net (code "180") (name "Net-(IC1-LX)") (class "Default")
      (node (ref "IC1") (pin "3") (pinfunction "LX_3") (pintype "power_in"))
      (node (ref "L1") (pin "P$1") (pinfunction "P$1_P$1") (pintype "passive"))
    )
    (net (code "181") (name "Net-(IC2-FB)") (class "Default")
      (node (ref "C7") (pin "1") (pinfunction "1_1") (pintype "passive"))
      (node (ref "IC2") (pin "5") (pinfunction "FB_5") (pintype "input"))
      (node (ref "R3") (pin "1") (pinfunction "1_1") (pintype "passive"))
      (node (ref "RN8") (pin "4") (pinfunction "1_4") (pintype "passive"))
    )
    (net (code "182") (name "Net-(IC2-LX)") (class "Default")
      (node (ref "IC2") (pin "3") (pinfunction "LX_3") (pintype "power_in"))
      (node (ref "L2") (pin "P$1") (pinfunction "P$1_P$1") (pintype "passive"))
    )
    (net (code "183") (name "Net-(L3-BC)") (class "Default")
      (node (ref "L3") (pin "B") (pinfunction "BC_B") (pintype "bidirectional"))
      (node (ref "RN1") (pin "4") (pinfunction "1_4") (pintype "passive"))
    )
    (net (code "184") (name "Net-(L3-GC)") (class "Default")
      (node (ref "L3") (pin "G") (pinfunction "GC_G") (pintype "bidirectional"))
      (node (ref "RN1") (pin "3") (pinfunction "1_3") (pintype "passive"))
    )
    (net (code "185") (name "Net-(L3-RC)") (class "Default")
      (node (ref "L3") (pin "R") (pinfunction "RC_R") (pintype "bidirectional"))
      (node (ref "RN1") (pin "2") (pinfunction "1_2") (pintype "passive"))
    )
    (net (code "186") (name "Net-(RN15A-2)") (class "Default")
      (node (ref "RN15") (pin "8") (pinfunction "2_8") (pintype "passive"))
      (node (ref "T1") (pin "P$13") (pinfunction "D10_P$13") (pintype "bidirectional"))
    )
    (net (code "187") (name "Net-(RN15B-2)") (class "Default")
      (node (ref "RN15") (pin "7") (pinfunction "2_7") (pintype "passive"))
      (node (ref "T1") (pin "P$37") (pinfunction "D9_P$37") (pintype "bidirectional"))
    )
    (net (code "188") (name "Net-(RN15C-2)") (class "Default")
      (node (ref "RN15") (pin "6") (pinfunction "2_6") (pintype "passive"))
      (node (ref "T1") (pin "P$12") (pinfunction "D8_P$12") (pintype "bidirectional"))
    )
    (net (code "189") (name "Net-(RN15D-2)") (class "Default")
      (node (ref "RN15") (pin "5") (pinfunction "2_5") (pintype "passive"))
      (node (ref "T1") (pin "P$38") (pinfunction "D12_P$38") (pintype "bidirectional"))
    )
    (net (code "190") (name "Net-(RN16A-2)") (class "Default")
      (node (ref "RN16") (pin "8") (pinfunction "2_8") (pintype "passive"))
      (node (ref "T1") (pin "P$11") (pinfunction "D6_P$11") (pintype "bidirectional"))
    )
    (net (code "191") (name "Net-(RN16B-2)") (class "Default")
      (node (ref "RN16") (pin "7") (pinfunction "2_7") (pintype "passive"))
      (node (ref "T1") (pin "P$36") (pinfunction "D7_P$36") (pintype "bidirectional"))
    )
    (net (code "192") (name "Net-(RN16C-2)") (class "Default")
      (node (ref "RN16") (pin "6") (pinfunction "2_6") (pintype "passive"))
      (node (ref "T1") (pin "P$10") (pinfunction "D4_P$10") (pintype "bidirectional"))
    )
    (net (code "193") (name "Net-(RN16D-2)") (class "Default")
      (node (ref "RN16") (pin "5") (pinfunction "2_5") (pintype "passive"))
      (node (ref "T1") (pin "P$35") (pinfunction "D5_P$35") (pintype "bidirectional"))
    )
    (net (code "194") (name "Net-(RN17A-2)") (class "Default")
      (node (ref "RN17") (pin "8") (pinfunction "2_8") (pintype "passive"))
      (node (ref "T1") (pin "P$9") (pinfunction "D2_P$9") (pintype "bidirectional"))
    )
    (net (code "195") (name "Net-(RN17B-2)") (class "Default")
      (node (ref "RN17") (pin "7") (pinfunction "2_7") (pintype "passive"))
      (node (ref "T1") (pin "P$34") (pinfunction "D3_P$34") (pintype "bidirectional"))
    )
    (net (code "196") (name "Net-(RN17C-2)") (class "Default")
      (node (ref "RN17") (pin "6") (pinfunction "2_6") (pintype "passive"))
      (node (ref "T1") (pin "P$8") (pinfunction "D0_P$8") (pintype "bidirectional"))
    )
    (net (code "197") (name "Net-(RN17D-2)") (class "Default")
      (node (ref "RN17") (pin "5") (pinfunction "2_5") (pintype "passive"))
      (node (ref "T1") (pin "P$33") (pinfunction "D1_P$33") (pintype "bidirectional"))
    )
    (net (code "198") (name "Net-(RN18B-1)") (class "Default")
      (node (ref "RN18") (pin "2") (pinfunction "1_2") (pintype "passive"))
      (node (ref "T2") (pin "P$37") (pinfunction "D9_P$37") (pintype "bidirectional"))
    )
    (net (code "199") (name "Net-(RN18C-1)") (class "Default")
      (node (ref "RN18") (pin "3") (pinfunction "1_3") (pintype "passive"))
      (node (ref "T2") (pin "P$13") (pinfunction "D10_P$13") (pintype "bidirectional"))
    )
    (net (code "200") (name "Net-(RN18D-1)") (class "Default")
      (node (ref "RN18") (pin "4") (pinfunction "1_4") (pintype "passive"))
      (node (ref "T2") (pin "P$38") (pinfunction "D12_P$38") (pintype "bidirectional"))
    )
    (net (code "201") (name "Net-(RN19B-1)") (class "Default")
      (node (ref "RN19") (pin "2") (pinfunction "1_2") (pintype "passive"))
      (node (ref "T2") (pin "P$35") (pinfunction "D5_P$35") (pintype "bidirectional"))
    )
    (net (code "202") (name "Net-(RN19C-1)") (class "Default")
      (node (ref "RN19") (pin "3") (pinfunction "1_3") (pintype "passive"))
      (node (ref "T2") (pin "P$11") (pinfunction "D6_P$11") (pintype "bidirectional"))
    )
    (net (code "203") (name "Net-(RN19D-1)") (class "Default")
      (node (ref "RN19") (pin "4") (pinfunction "1_4") (pintype "passive"))
      (node (ref "T2") (pin "P$36") (pinfunction "D7_P$36") (pintype "bidirectional"))
    )
    (net (code "204") (name "Net-(RN20B-1)") (class "Default")
      (node (ref "RN20") (pin "2") (pinfunction "1_2") (pintype "passive"))
      (node (ref "T2") (pin "P$33") (pinfunction "D1_P$33") (pintype "bidirectional"))
    )
    (net (code "205") (name "Net-(RN20C-1)") (class "Default")
      (node (ref "RN20") (pin "3") (pinfunction "1_3") (pintype "passive"))
      (node (ref "T2") (pin "P$9") (pinfunction "D2_P$9") (pintype "bidirectional"))
    )
    (net (code "206") (name "Net-(RN20D-1)") (class "Default")
      (node (ref "RN20") (pin "4") (pinfunction "1_4") (pintype "passive"))
      (node (ref "T2") (pin "P$34") (pinfunction "D3_P$34") (pintype "bidirectional"))
    )
    (net (code "207") (name "Net-(RN21A-2)") (class "Default")
      (node (ref "RN21") (pin "8") (pinfunction "2_8") (pintype "passive"))
      (node (ref "T4") (pin "P$13") (pinfunction "D10_P$13") (pintype "bidirectional"))
    )
    (net (code "208") (name "Net-(RN21B-2)") (class "Default")
      (node (ref "RN21") (pin "7") (pinfunction "2_7") (pintype "passive"))
      (node (ref "T4") (pin "P$38") (pinfunction "D12_P$38") (pintype "bidirectional"))
    )
    (net (code "209") (name "Net-(RN21C-2)") (class "Default")
      (node (ref "RN21") (pin "6") (pinfunction "2_6") (pintype "passive"))
      (node (ref "T4") (pin "P$12") (pinfunction "D8_P$12") (pintype "bidirectional"))
    )
    (net (code "210") (name "Net-(RN21D-2)") (class "Default")
      (node (ref "RN21") (pin "5") (pinfunction "2_5") (pintype "passive"))
      (node (ref "T4") (pin "P$37") (pinfunction "D9_P$37") (pintype "bidirectional"))
    )
    (net (code "211") (name "Net-(RN22A-2)") (class "Default")
      (node (ref "RN22") (pin "8") (pinfunction "2_8") (pintype "passive"))
      (node (ref "T4") (pin "P$11") (pinfunction "D6_P$11") (pintype "bidirectional"))
    )
    (net (code "212") (name "Net-(RN22B-2)") (class "Default")
      (node (ref "RN22") (pin "7") (pinfunction "2_7") (pintype "passive"))
      (node (ref "T4") (pin "P$36") (pinfunction "D7_P$36") (pintype "bidirectional"))
    )
    (net (code "213") (name "Net-(RN22C-2)") (class "Default")
      (node (ref "RN22") (pin "6") (pinfunction "2_6") (pintype "passive"))
      (node (ref "T4") (pin "P$10") (pinfunction "D4_P$10") (pintype "bidirectional"))
    )
    (net (code "214") (name "Net-(RN22D-2)") (class "Default")
      (node (ref "RN22") (pin "5") (pinfunction "2_5") (pintype "passive"))
      (node (ref "T4") (pin "P$35") (pinfunction "D5_P$35") (pintype "bidirectional"))
    )
    (net (code "215") (name "Net-(RN23A-2)") (class "Default")
      (node (ref "RN23") (pin "8") (pinfunction "2_8") (pintype "passive"))
      (node (ref "T4") (pin "P$9") (pinfunction "D2_P$9") (pintype "bidirectional"))
    )
    (net (code "216") (name "Net-(RN23B-2)") (class "Default")
      (node (ref "RN23") (pin "7") (pinfunction "2_7") (pintype "passive"))
      (node (ref "T4") (pin "P$34") (pinfunction "D3_P$34") (pintype "bidirectional"))
    )
    (net (code "217") (name "Net-(RN23C-2)") (class "Default")
      (node (ref "RN23") (pin "6") (pinfunction "2_6") (pintype "passive"))
      (node (ref "T4") (pin "P$8") (pinfunction "D0_P$8") (pintype "bidirectional"))
    )
    (net (code "218") (name "Net-(RN23D-2)") (class "Default")
      (node (ref "RN23") (pin "5") (pinfunction "2_5") (pintype "passive"))
      (node (ref "T4") (pin "P$33") (pinfunction "D1_P$33") (pintype "bidirectional"))
    )
    (net (code "219") (name "Net-(RN24B-1)") (class "Default")
      (node (ref "RN24") (pin "2") (pinfunction "1_2") (pintype "passive"))
      (node (ref "T5") (pin "P$37") (pinfunction "D9_P$37") (pintype "bidirectional"))
    )
    (net (code "220") (name "Net-(RN24C-1)") (class "Default")
      (node (ref "RN24") (pin "3") (pinfunction "1_3") (pintype "passive"))
      (node (ref "T5") (pin "P$13") (pinfunction "D10_P$13") (pintype "bidirectional"))
    )
    (net (code "221") (name "Net-(RN24D-1)") (class "Default")
      (node (ref "RN24") (pin "4") (pinfunction "1_4") (pintype "passive"))
      (node (ref "T5") (pin "P$38") (pinfunction "D12_P$38") (pintype "bidirectional"))
    )
    (net (code "222") (name "Net-(RN25B-1)") (class "Default")
      (node (ref "RN25") (pin "2") (pinfunction "1_2") (pintype "passive"))
      (node (ref "T5") (pin "P$35") (pinfunction "D5_P$35") (pintype "bidirectional"))
    )
    (net (code "223") (name "Net-(RN25C-1)") (class "Default")
      (node (ref "RN25") (pin "3") (pinfunction "1_3") (pintype "passive"))
      (node (ref "T5") (pin "P$11") (pinfunction "D6_P$11") (pintype "bidirectional"))
    )
    (net (code "224") (name "Net-(RN25D-1)") (class "Default")
      (node (ref "RN25") (pin "4") (pinfunction "1_4") (pintype "passive"))
      (node (ref "T5") (pin "P$36") (pinfunction "D7_P$36") (pintype "bidirectional"))
    )
    (net (code "225") (name "Net-(RN26B-1)") (class "Default")
      (node (ref "RN26") (pin "2") (pinfunction "1_2") (pintype "passive"))
      (node (ref "T5") (pin "P$33") (pinfunction "D1_P$33") (pintype "bidirectional"))
    )
    (net (code "226") (name "Net-(RN26C-1)") (class "Default")
      (node (ref "RN26") (pin "3") (pinfunction "1_3") (pintype "passive"))
      (node (ref "T5") (pin "P$9") (pinfunction "D2_P$9") (pintype "bidirectional"))
    )
    (net (code "227") (name "Net-(RN26D-1)") (class "Default")
      (node (ref "RN26") (pin "4") (pinfunction "1_4") (pintype "passive"))
      (node (ref "T5") (pin "P$34") (pinfunction "D3_P$34") (pintype "bidirectional"))
    )
    (net (code "228") (name "Net-(T2-D0)") (class "Default")
      (node (ref "RN20") (pin "1") (pinfunction "1_1") (pintype "passive"))
      (node (ref "T2") (pin "P$8") (pinfunction "D0_P$8") (pintype "bidirectional"))
    )
    (net (code "229") (name "Net-(T2-D4)") (class "Default")
      (node (ref "RN19") (pin "1") (pinfunction "1_1") (pintype "passive"))
      (node (ref "T2") (pin "P$10") (pinfunction "D4_P$10") (pintype "bidirectional"))
    )
    (net (code "230") (name "Net-(T2-D8)") (class "Default")
      (node (ref "RN18") (pin "1") (pinfunction "1_1") (pintype "passive"))
      (node (ref "T2") (pin "P$12") (pinfunction "D8_P$12") (pintype "bidirectional"))
    )
    (net (code "231") (name "Net-(T5-D0)") (class "Default")
      (node (ref "RN26") (pin "1") (pinfunction "1_1") (pintype "passive"))
      (node (ref "T5") (pin "P$8") (pinfunction "D0_P$8") (pintype "bidirectional"))
    )
    (net (code "232") (name "Net-(T5-D4)") (class "Default")
      (node (ref "RN25") (pin "1") (pinfunction "1_1") (pintype "passive"))
      (node (ref "T5") (pin "P$10") (pinfunction "D4_P$10") (pintype "bidirectional"))
    )
    (net (code "233") (name "Net-(T5-D8)") (class "Default")
      (node (ref "RN24") (pin "1") (pinfunction "1_1") (pintype "passive"))
      (node (ref "T5") (pin "P$12") (pinfunction "D8_P$12") (pintype "bidirectional"))
    )
    (net (code "234") (name "unconnected-(IC3-VPP_FAST-PadB10)") (class "Default")
      (node (ref "IC3") (pin "B10") (pinfunction "VPP_FAST_B10") (pintype "bidirectional"))
    )
    (net (code "235") (name "unconnected-(IC10-N{slash}C-Pad15)") (class "Default")
      (node (ref "IC10") (pin "15") (pinfunction "N/C_15") (pintype "no_connect"))
    )
    (net (code "236") (name "unconnected-(RN2-Pad1)") (class "Default")
      (node (ref "RN2") (pin "1") (pinfunction "1_1") (pintype "passive"))
    )
    (net (code "237") (name "unconnected-(RN2A-2-Pad8)") (class "Default")
      (node (ref "RN2") (pin "8") (pinfunction "2_8") (pintype "passive"))
    )
    (net (code "238") (name "unconnected-(RN2B-1-Pad2)") (class "Default")
      (node (ref "RN2") (pin "2") (pinfunction "1_2") (pintype "passive"))
    )
    (net (code "239") (name "unconnected-(RN2B-2-Pad7)") (class "Default")
      (node (ref "RN2") (pin "7") (pinfunction "2_7") (pintype "passive"))
    )
    (net (code "240") (name "unconnected-(RN14C-1-Pad3)") (class "Default")
      (node (ref "RN14") (pin "3") (pinfunction "1_3") (pintype "passive"))
    )
    (net (code "241") (name "unconnected-(RN14C-2-Pad6)") (class "Default")
      (node (ref "RN14") (pin "6") (pinfunction "2_6") (pintype "passive"))
    )
    (net (code "242") (name "unconnected-(RN14D-1-Pad4)") (class "Default")
      (node (ref "RN14") (pin "4") (pinfunction "1_4") (pintype "passive"))
    )
    (net (code "243") (name "unconnected-(RN14D-2-Pad5)") (class "Default")
      (node (ref "RN14") (pin "5") (pinfunction "2_5") (pintype "passive"))
    )
    (net (code "244") (name "unconnected-(U$2-P$1-PadP$3)") (class "Default")
      (node (ref "U$2") (pin "P$3") (pinfunction "P$1_P$3") (pintype "no_connect"))
    )
    (net (code "245") (name "unconnected-(U$2-P$2-PadP$4)") (class "Default")
      (node (ref "U$2") (pin "P$4") (pinfunction "P$2_P$4") (pintype "no_connect"))
    )
  )
)
